# pcb-pick-plaz-control_v1d.net
KiCad netlist of a schematic drawn in EAGLE
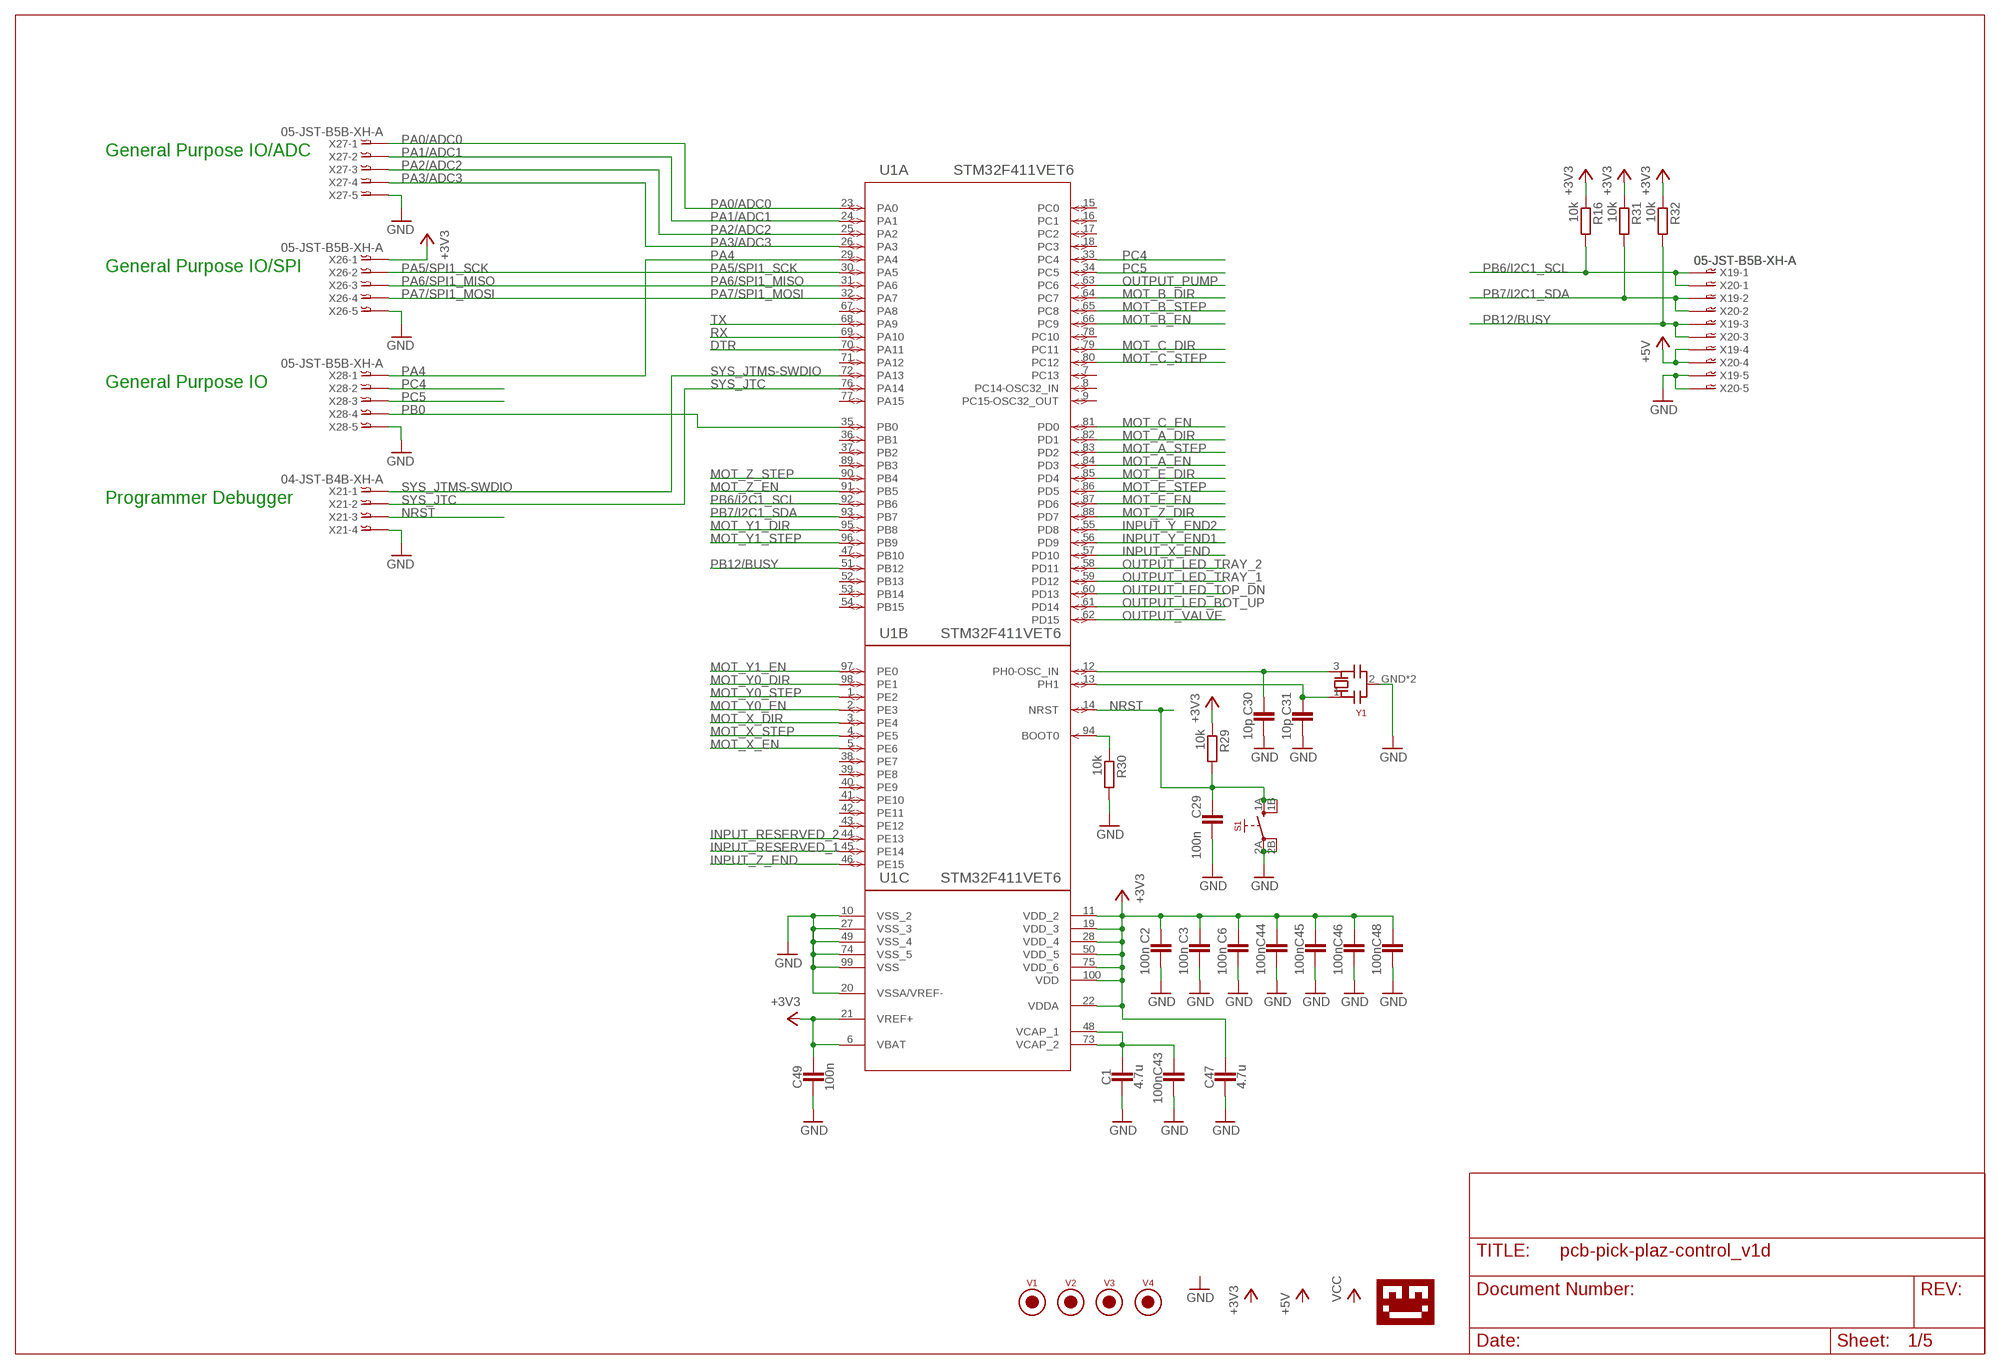
[diagram p0: schematic, sheet 1]
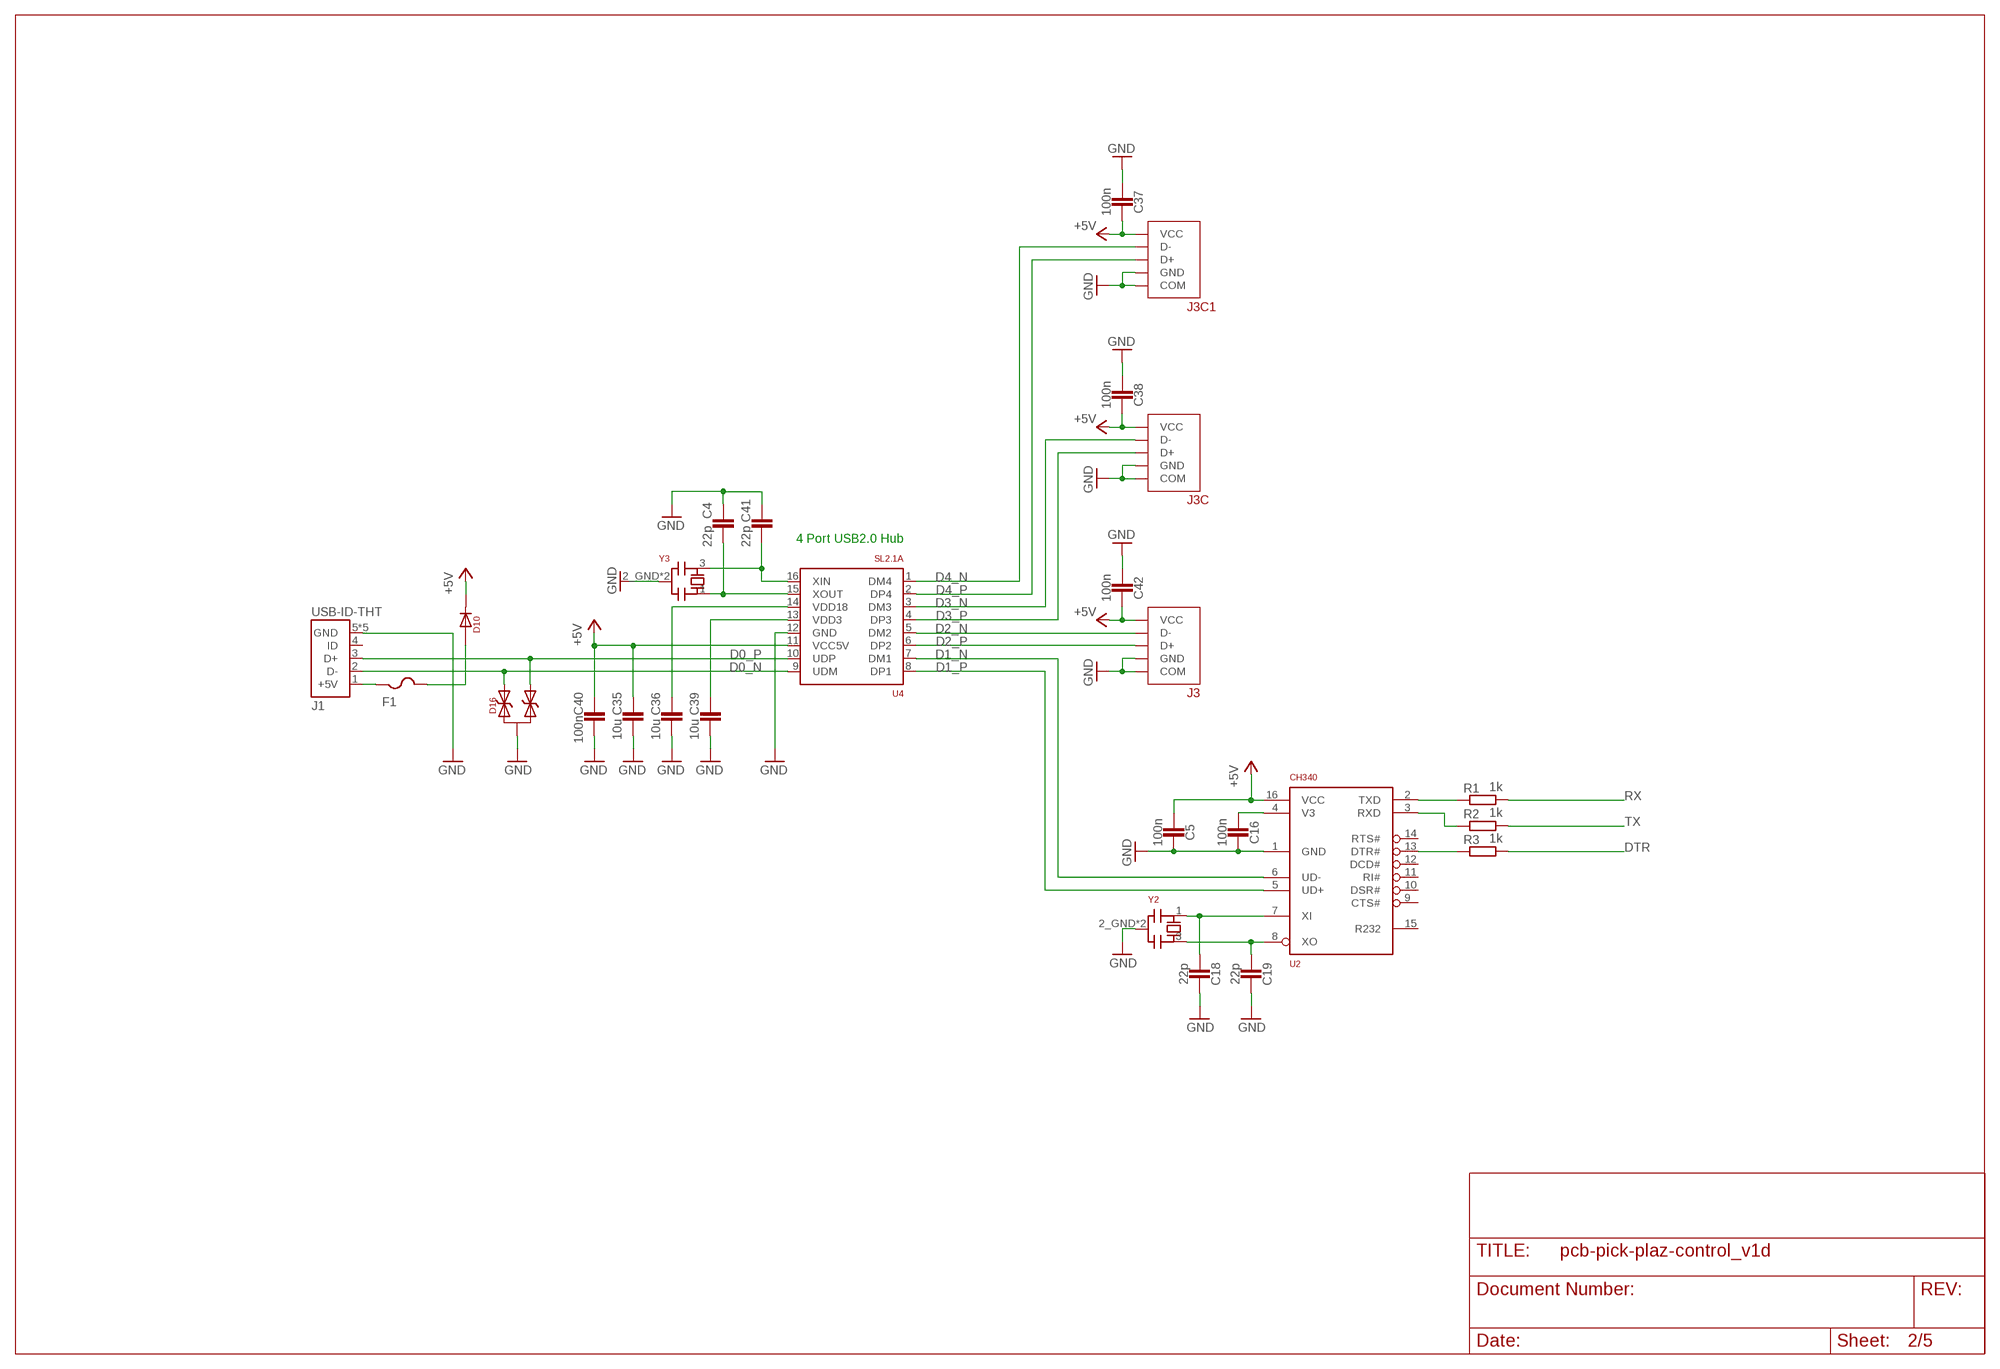
[diagram p1: schematic, sheet 2]
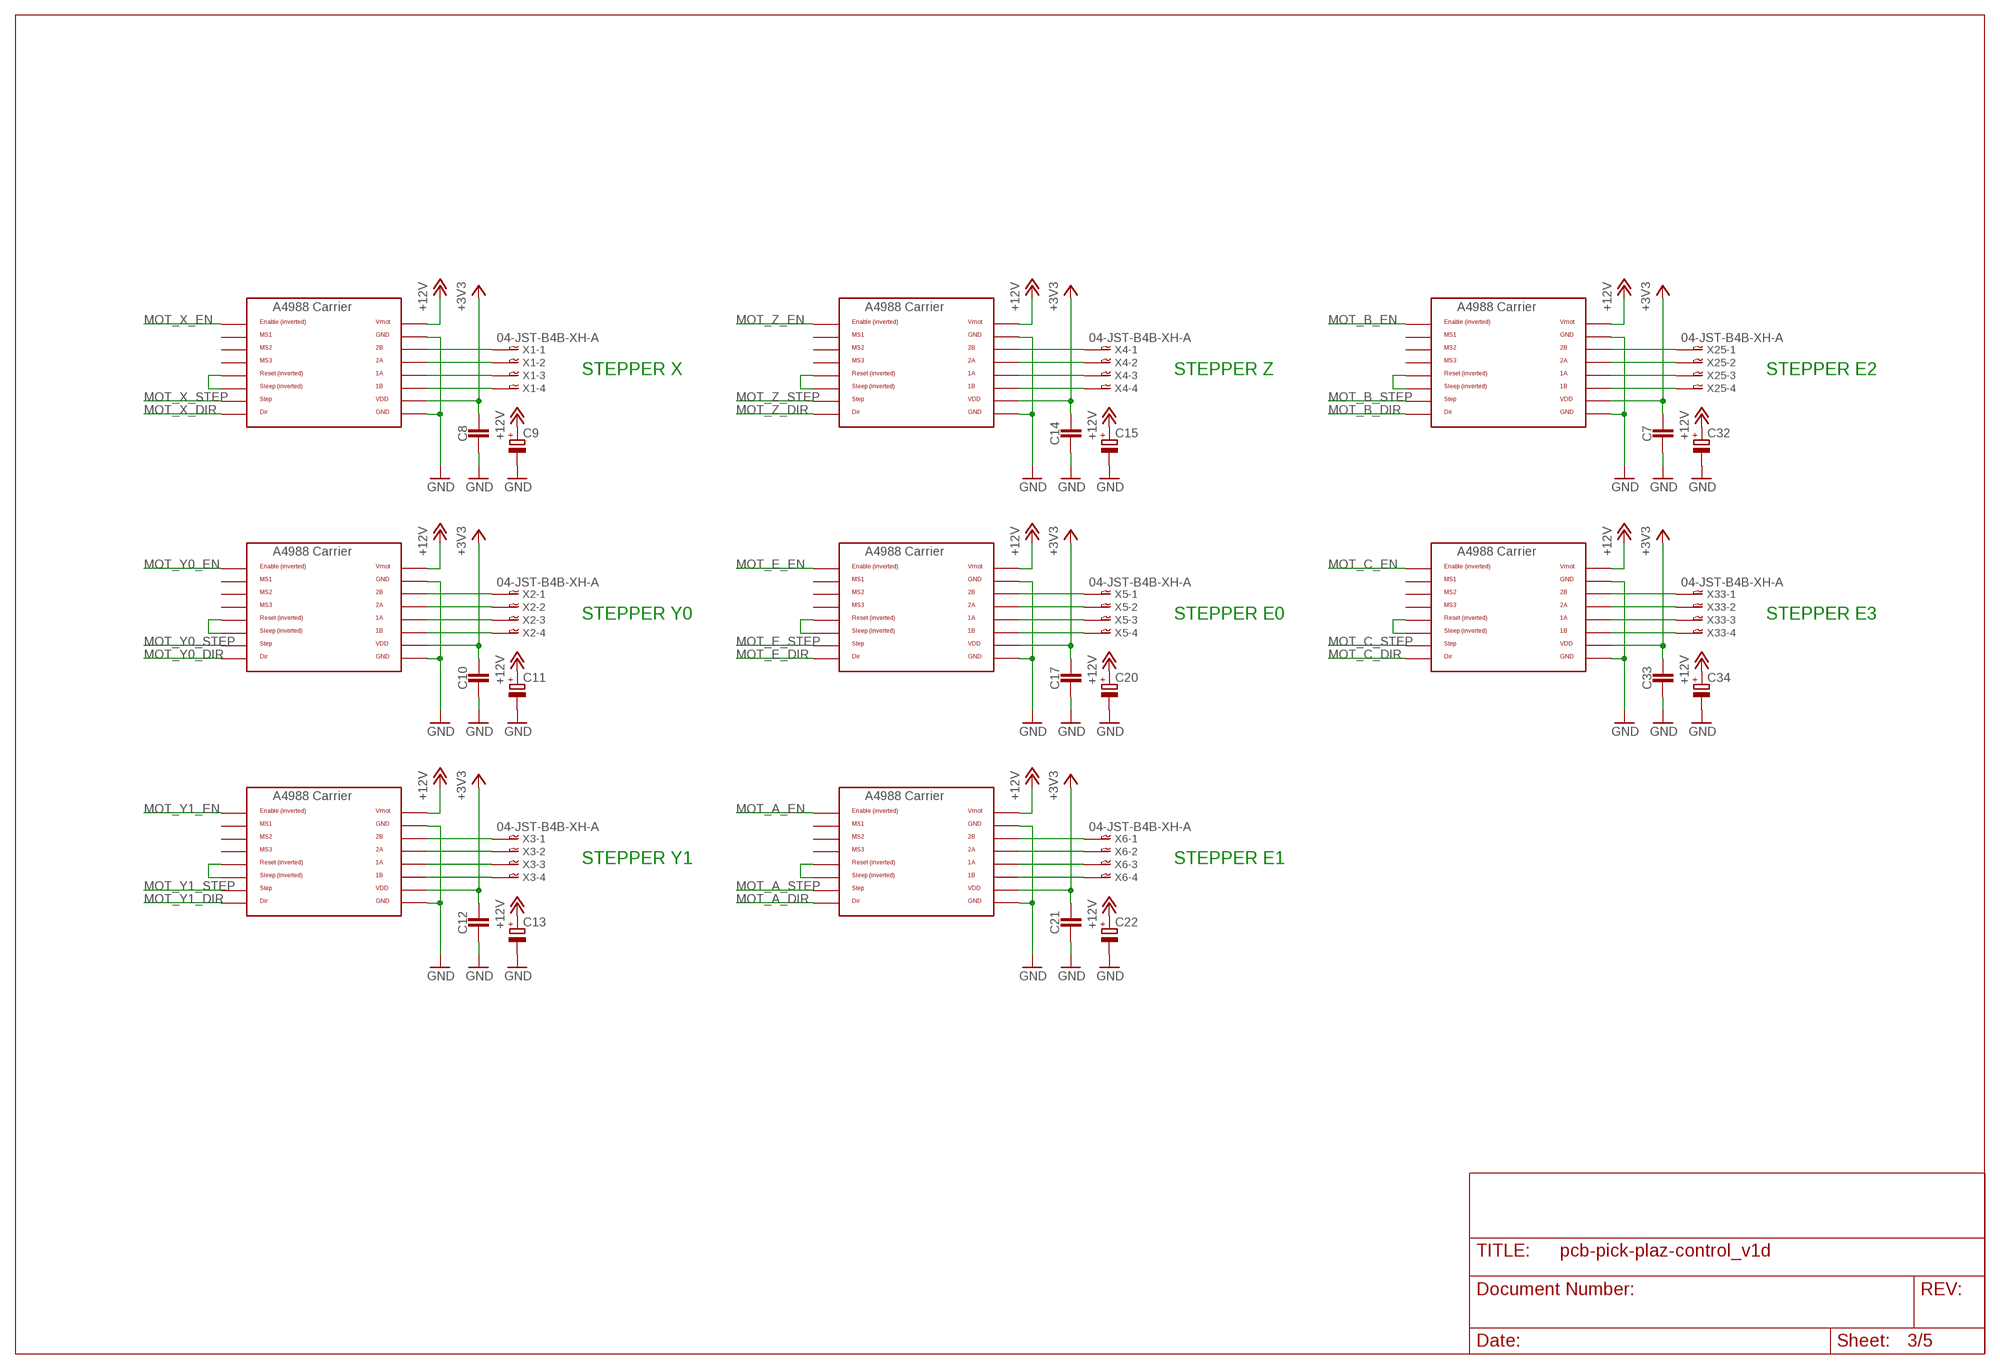
[diagram p2: schematic, sheet 3]
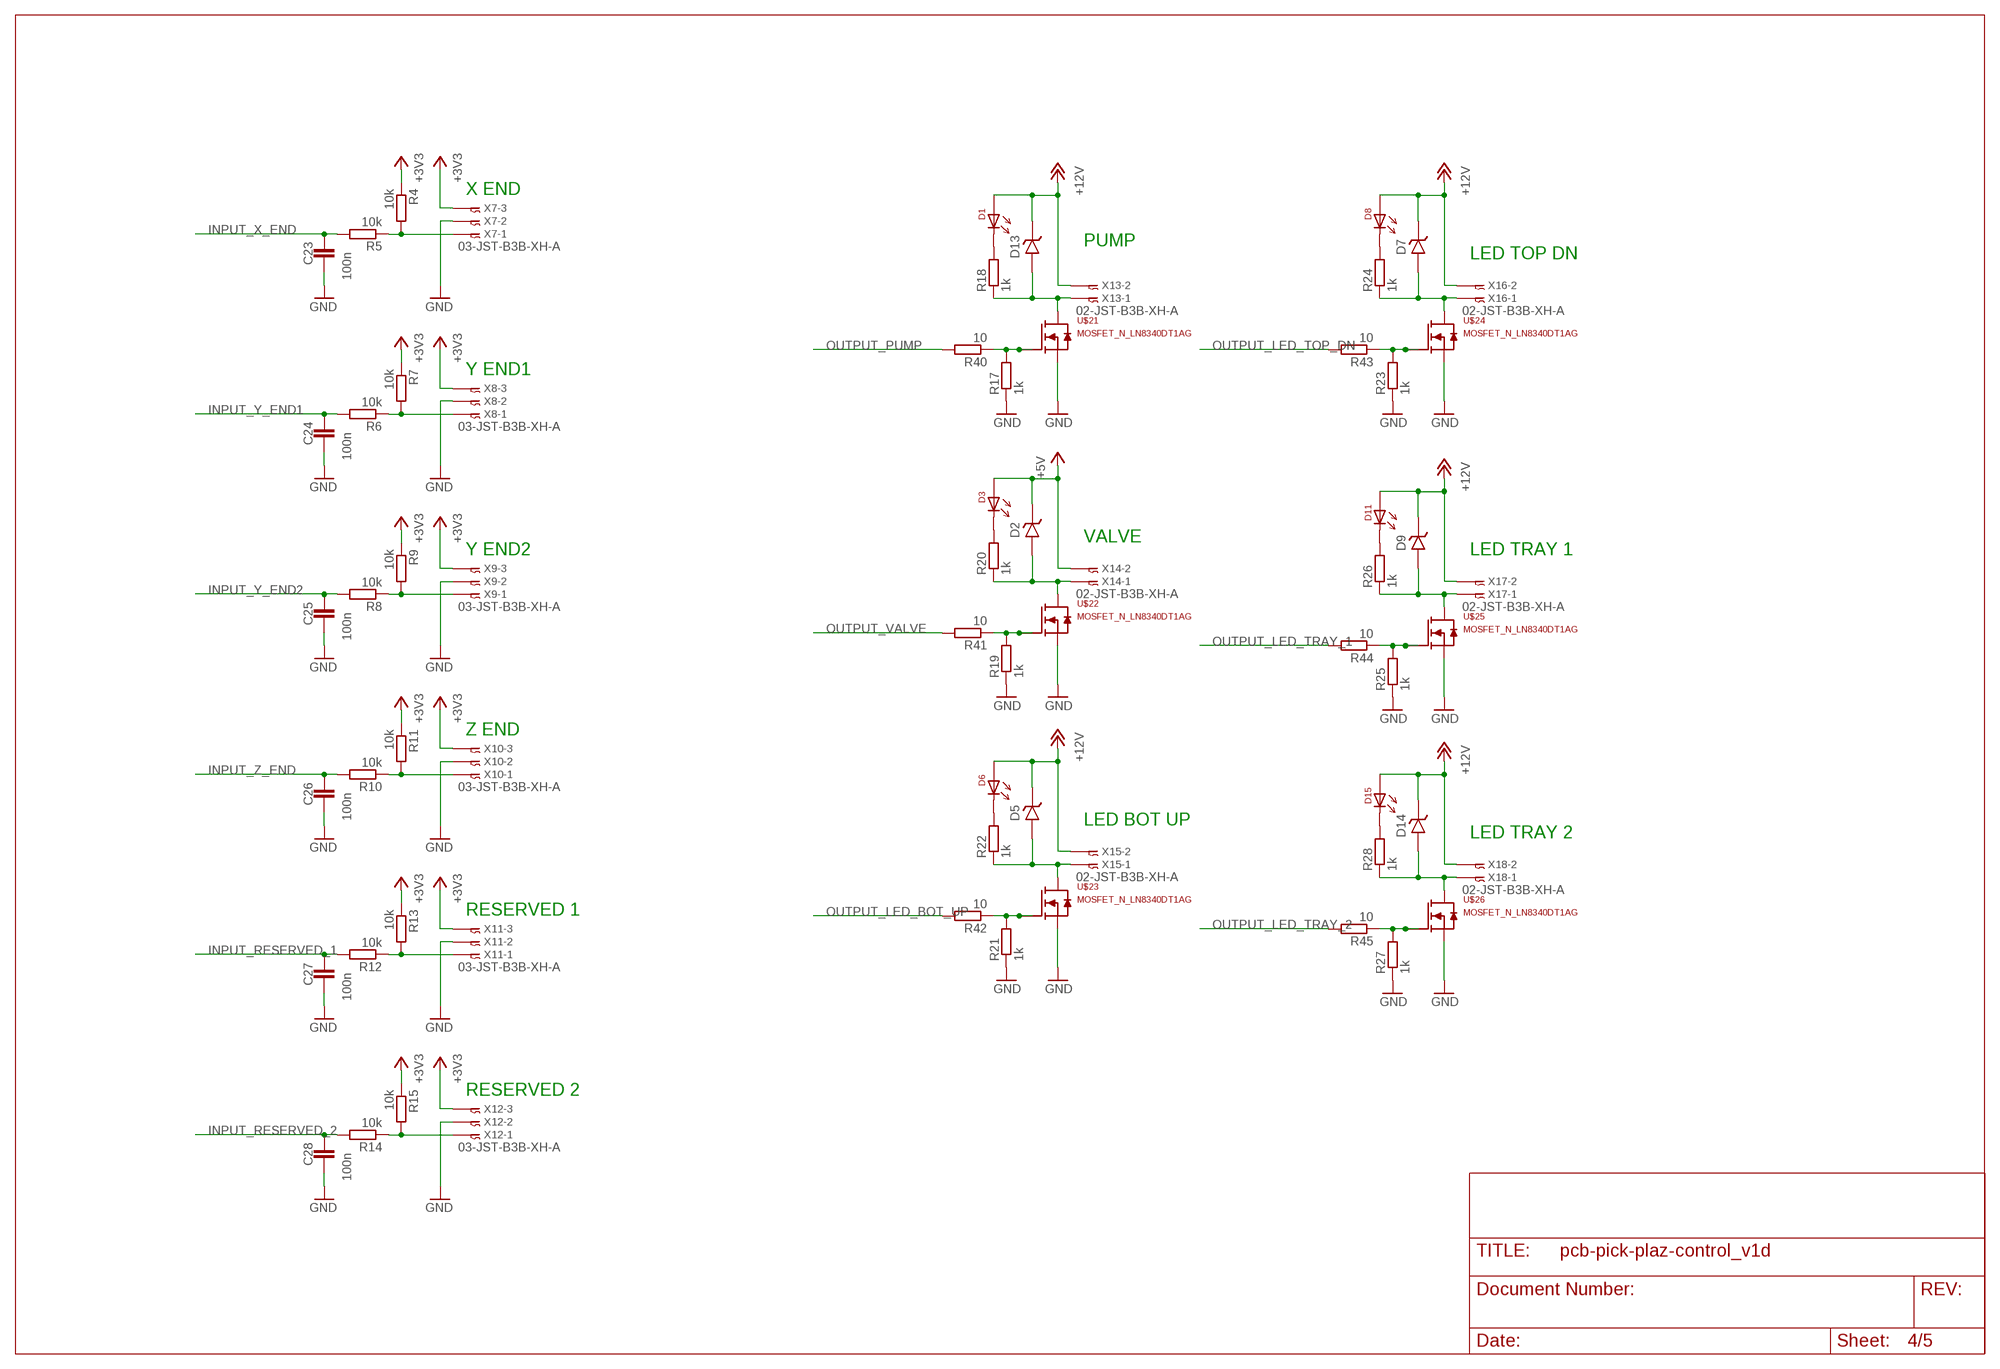
[diagram p3: schematic, sheet 4]
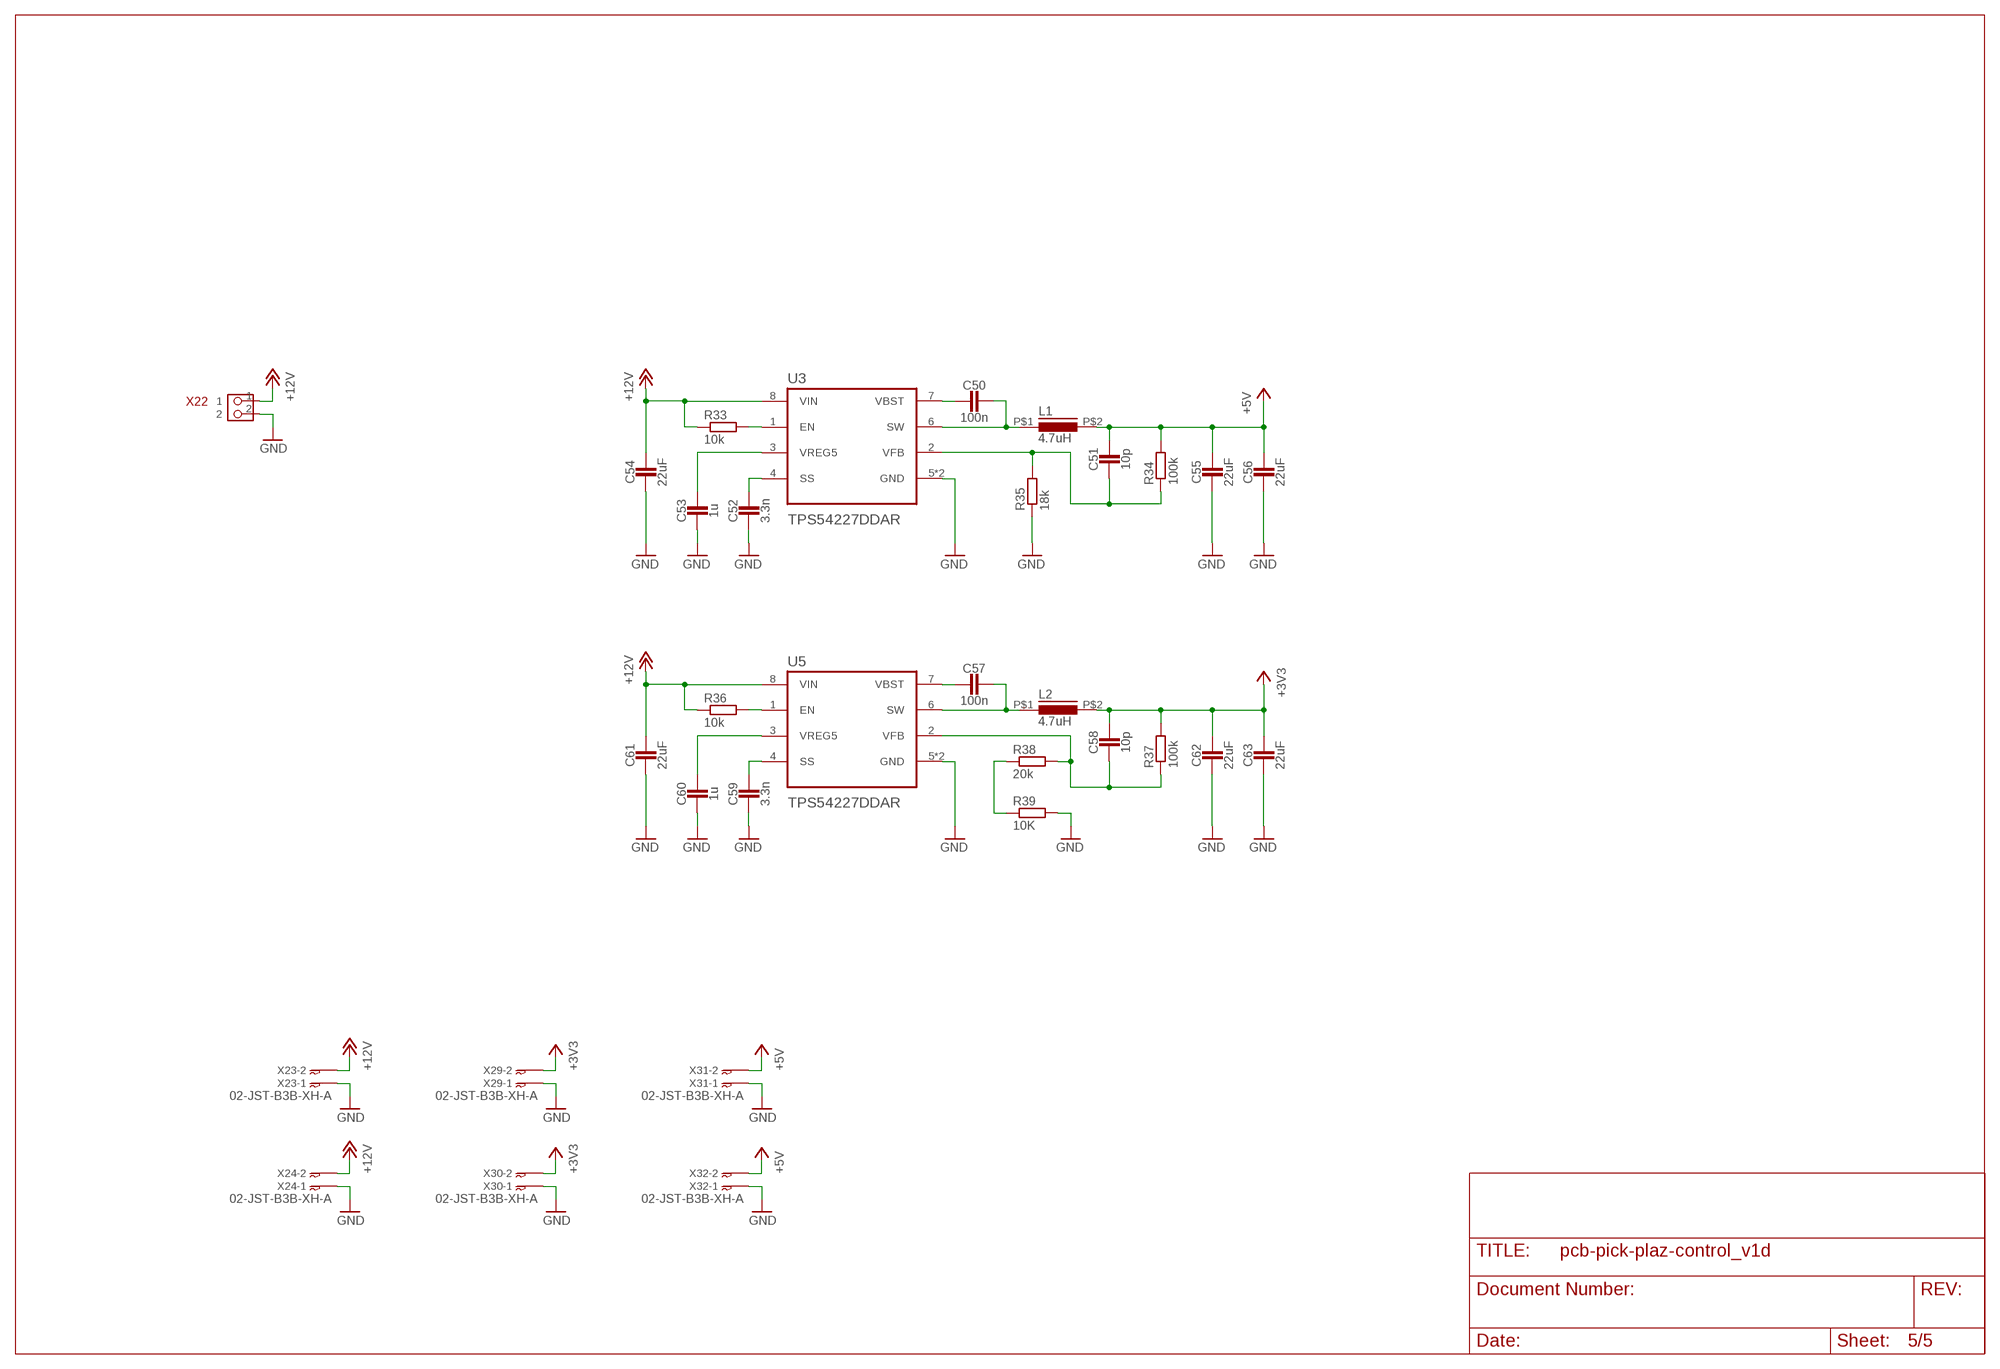
[diagram p4: schematic, sheet 5]

(export (version "E")
  (design (tool "Eeschema 10.0.6"))
  (components
    (comp (ref "C1")
      (value "4.7u")
      (footprint "eagle-import:0805_CAP")
      (libsource (lib "eagle-import") (part "CAPACITOR0805_CAP"))
    )
    (comp (ref "C2")
      (value "100n")
      (footprint "eagle-import:0603_CAP")
      (libsource (lib "eagle-import") (part "CAPACITOR0603_CAP"))
    )
    (comp (ref "C3")
      (value "100n")
      (footprint "eagle-import:0603_CAP")
      (libsource (lib "eagle-import") (part "CAPACITOR0603_CAP"))
    )
    (comp (ref "C6")
      (value "100n")
      (footprint "eagle-import:0603_CAP")
      (libsource (lib "eagle-import") (part "CAPACITOR0603_CAP"))
    )
    (comp (ref "C29")
      (value "100n")
      (footprint "eagle-import:0603_CAP")
      (libsource (lib "eagle-import") (part "CAPACITOR0603_CAP"))
    )
    (comp (ref "C30")
      (value "10p")
      (footprint "eagle-import:0603_CAP")
      (libsource (lib "eagle-import") (part "CAPACITOR0603_CAP"))
    )
    (comp (ref "C31")
      (value "10p")
      (footprint "eagle-import:0603_CAP")
      (libsource (lib "eagle-import") (part "CAPACITOR0603_CAP"))
    )
    (comp (ref "C43")
      (value "100n")
      (footprint "eagle-import:0603_CAP")
      (libsource (lib "eagle-import") (part "CAPACITOR0603_CAP"))
    )
    (comp (ref "C44")
      (value "100n")
      (footprint "eagle-import:0603_CAP")
      (libsource (lib "eagle-import") (part "CAPACITOR0603_CAP"))
    )
    (comp (ref "C45")
      (value "100n")
      (footprint "eagle-import:0603_CAP")
      (libsource (lib "eagle-import") (part "CAPACITOR0603_CAP"))
    )
    (comp (ref "C46")
      (value "100n")
      (footprint "eagle-import:0603_CAP")
      (libsource (lib "eagle-import") (part "CAPACITOR0603_CAP"))
    )
    (comp (ref "C47")
      (value "4.7u")
      (footprint "eagle-import:0805_CAP")
      (libsource (lib "eagle-import") (part "CAPACITOR0805_CAP"))
    )
    (comp (ref "C48")
      (value "100n")
      (footprint "eagle-import:0603_CAP")
      (libsource (lib "eagle-import") (part "CAPACITOR0603_CAP"))
    )
    (comp (ref "C49")
      (value "100n")
      (footprint "eagle-import:0603_CAP")
      (libsource (lib "eagle-import") (part "CAPACITOR0603_CAP"))
    )
    (comp (ref "R16")
      (value "10k")
      (footprint "eagle-import:0603-RES")
      (libsource (lib "eagle-import") (part "RESISTOR0603_RES"))
    )
    (comp (ref "R29")
      (value "10k")
      (footprint "eagle-import:0603-RES")
      (libsource (lib "eagle-import") (part "RESISTOR0603_RES"))
    )
    (comp (ref "R30")
      (value "10k")
      (footprint "eagle-import:0603-RES")
      (libsource (lib "eagle-import") (part "RESISTOR0603_RES"))
    )
    (comp (ref "R31")
      (value "10k")
      (footprint "eagle-import:0603-RES")
      (libsource (lib "eagle-import") (part "RESISTOR0603_RES"))
    )
    (comp (ref "R32")
      (value "10k")
      (footprint "eagle-import:0603-RES")
      (libsource (lib "eagle-import") (part "RESISTOR0603_RES"))
    )
    (comp (ref "S1")
      (value "SWITCH_2PD")
      (footprint "eagle-import:SWITCH_WH")
      (libsource (lib "eagle-import") (part "SWITCH_2PD"))
    )
    (comp (ref "U$1")
      (value "LOGO-TOBENG-1MM-FINISH")
      (footprint "eagle-import:TOBENG-1MM-FINISH")
      (libsource (lib "eagle-import") (part "LOGO-TOBENG-1MM-FINISH"))
    )
    (comp (ref "U1")
      (value "STM32F411VET6")
      (footprint "eagle-import:LQFP100-14X14MM")
      (fields (field (name "COPYRIGHT") "Copyright (C) 2018 Accelerated Designs. All rights reserved"))
      (libsource (lib "eagle-import") (part "STM32F411VET6"))
    )
    (comp (ref "V1")
      (value "FIDUCIAL2MM")
      (footprint "eagle-import:FIDUCIAL_2MM")
      (libsource (lib "eagle-import") (part "FIDUCIAL2MM"))
    )
    (comp (ref "V2")
      (value "FIDUCIAL2MM")
      (footprint "eagle-import:FIDUCIAL_2MM")
      (libsource (lib "eagle-import") (part "FIDUCIAL2MM"))
    )
    (comp (ref "V3")
      (value "FIDUCIAL2MM")
      (footprint "eagle-import:FIDUCIAL_2MM")
      (libsource (lib "eagle-import") (part "FIDUCIAL2MM"))
    )
    (comp (ref "V4")
      (value "FIDUCIAL2MM")
      (footprint "eagle-import:FIDUCIAL_2MM")
      (libsource (lib "eagle-import") (part "FIDUCIAL2MM"))
    )
    (comp (ref "X19")
      (value "05-JST-B5B-XH-A")
      (footprint "eagle-import:B5B-XH")
      (libsource (lib "eagle-import") (part "05-JST-B5B-XH-A"))
    )
    (comp (ref "X20")
      (value "05-JST-B5B-XH-A")
      (footprint "eagle-import:B5B-XH")
      (libsource (lib "eagle-import") (part "05-JST-B5B-XH-A"))
    )
    (comp (ref "X21")
      (value "04-JST-B4B-XH-A")
      (footprint "eagle-import:B4B-XH")
      (libsource (lib "eagle-import") (part "04-JST-B4B-XH-A"))
    )
    (comp (ref "X26")
      (value "05-JST-B5B-XH-A")
      (footprint "eagle-import:B5B-XH")
      (libsource (lib "eagle-import") (part "05-JST-B5B-XH-A"))
    )
    (comp (ref "X27")
      (value "05-JST-B5B-XH-A")
      (footprint "eagle-import:B5B-XH")
      (libsource (lib "eagle-import") (part "05-JST-B5B-XH-A"))
    )
    (comp (ref "X28")
      (value "05-JST-B5B-XH-A")
      (footprint "eagle-import:B5B-XH")
      (libsource (lib "eagle-import") (part "05-JST-B5B-XH-A"))
    )
    (comp (ref "Y1")
      (value "3213-QUARZ3225")
      (footprint "eagle-import:3225-QUARZ")
      (libsource (lib "eagle-import") (part "3213-QUARZ3225"))
    )
    (comp (ref "C4")
      (value "22p")
      (footprint "eagle-import:0603_CAP")
      (libsource (lib "eagle-import") (part "CAPACITOR0603_CAP"))
    )
    (comp (ref "C5")
      (value "100n")
      (footprint "eagle-import:0603_CAP")
      (libsource (lib "eagle-import") (part "CAPACITOR0603_CAP"))
    )
    (comp (ref "C16")
      (value "100n")
      (footprint "eagle-import:0603_CAP")
      (libsource (lib "eagle-import") (part "CAPACITOR0603_CAP"))
    )
    (comp (ref "C18")
      (value "22p")
      (footprint "eagle-import:0603_CAP")
      (libsource (lib "eagle-import") (part "CAPACITOR0603_CAP"))
    )
    (comp (ref "C19")
      (value "22p")
      (footprint "eagle-import:0603_CAP")
      (libsource (lib "eagle-import") (part "CAPACITOR0603_CAP"))
    )
    (comp (ref "C35")
      (value "10u")
      (footprint "eagle-import:0805_CAP")
      (libsource (lib "eagle-import") (part "CAPACITOR0805_CAP"))
    )
    (comp (ref "C36")
      (value "10u")
      (footprint "eagle-import:0805_CAP")
      (libsource (lib "eagle-import") (part "CAPACITOR0805_CAP"))
    )
    (comp (ref "C37")
      (value "100n")
      (footprint "eagle-import:0603_CAP")
      (libsource (lib "eagle-import") (part "CAPACITOR0603_CAP"))
    )
    (comp (ref "C38")
      (value "100n")
      (footprint "eagle-import:0603_CAP")
      (libsource (lib "eagle-import") (part "CAPACITOR0603_CAP"))
    )
    (comp (ref "C39")
      (value "10u")
      (footprint "eagle-import:0805_CAP")
      (libsource (lib "eagle-import") (part "CAPACITOR0805_CAP"))
    )
    (comp (ref "C40")
      (value "100n")
      (footprint "eagle-import:0603_CAP")
      (libsource (lib "eagle-import") (part "CAPACITOR0603_CAP"))
    )
    (comp (ref "C41")
      (value "22p")
      (footprint "eagle-import:0603_CAP")
      (libsource (lib "eagle-import") (part "CAPACITOR0603_CAP"))
    )
    (comp (ref "C42")
      (value "100n")
      (footprint "eagle-import:0603_CAP")
      (libsource (lib "eagle-import") (part "CAPACITOR0603_CAP"))
    )
    (comp (ref "D10")
      (value "DIODE-1206")
      (footprint "eagle-import:1206-DOT")
      (libsource (lib "eagle-import") (part "DIODE-1206"))
    )
    (comp (ref "D16")
      (value "DIODE-TVS")
      (footprint "eagle-import:SOT-23")
      (libsource (lib "eagle-import") (part "DIODE-TVS"))
    )
    (comp (ref "F1")
      (value "PTCFUSE-1206")
      (footprint "eagle-import:R1206")
      (libsource (lib "eagle-import") (part "PTCFUSE-1206"))
    )
    (comp (ref "J1")
      (value "USB-ID-THT")
      (footprint "eagle-import:USB-MICRO-THT")
      (libsource (lib "eagle-import") (part "USB-ID-THT"))
    )
    (comp (ref "J3")
      (value "USB-LCSC_C42431")
      (footprint "eagle-import:USB-A-LCSC_C42431")
      (libsource (lib "eagle-import") (part "USB-LCSC_C42431"))
    )
    (comp (ref "J3C")
      (value "USB-LCSC_C42431")
      (footprint "eagle-import:USB-A-LCSC_C42431")
      (libsource (lib "eagle-import") (part "USB-LCSC_C42431"))
    )
    (comp (ref "J3C1")
      (value "USB-LCSC_C42431")
      (footprint "eagle-import:USB-A-LCSC_C42431")
      (libsource (lib "eagle-import") (part "USB-LCSC_C42431"))
    )
    (comp (ref "R1")
      (value "1k")
      (footprint "eagle-import:0603-RES")
      (libsource (lib "eagle-import") (part "RESISTOR0603_RES"))
    )
    (comp (ref "R2")
      (value "1k")
      (footprint "eagle-import:0603-RES")
      (libsource (lib "eagle-import") (part "RESISTOR0603_RES"))
    )
    (comp (ref "R3")
      (value "1k")
      (footprint "eagle-import:0603-RES")
      (libsource (lib "eagle-import") (part "RESISTOR0603_RES"))
    )
    (comp (ref "U2")
      (value "CH340")
      (footprint "eagle-import:SOIC-16")
      (libsource (lib "eagle-import") (part "CH340"))
    )
    (comp (ref "U4")
      (value "SL2.1A")
      (footprint "eagle-import:SOIC-16")
      (libsource (lib "eagle-import") (part "SL2.1A"))
    )
    (comp (ref "Y2")
      (value "3213-QUARZ3225")
      (footprint "eagle-import:3225-QUARZ")
      (libsource (lib "eagle-import") (part "3213-QUARZ3225"))
    )
    (comp (ref "Y3")
      (value "3213-QUARZ3225")
      (footprint "eagle-import:3225-QUARZ")
      (libsource (lib "eagle-import") (part "3213-QUARZ3225"))
    )
    (comp (ref "C7")
      (value "CAPACITOR0603_CAP")
      (footprint "eagle-import:0603_CAP")
      (libsource (lib "eagle-import") (part "CAPACITOR0603_CAP"))
    )
    (comp (ref "C8")
      (value "CAPACITOR0603_CAP")
      (footprint "eagle-import:0603_CAP")
      (libsource (lib "eagle-import") (part "CAPACITOR0603_CAP"))
    )
    (comp (ref "C9")
      (value "CPOL-EU175TMP-0808")
      (footprint "eagle-import:175TMP-0808")
      (libsource (lib "eagle-import") (part "CPOL-EU175TMP-0808"))
    )
    (comp (ref "C10")
      (value "CAPACITOR0603_CAP")
      (footprint "eagle-import:0603_CAP")
      (libsource (lib "eagle-import") (part "CAPACITOR0603_CAP"))
    )
    (comp (ref "C11")
      (value "CPOL-EU175TMP-0808")
      (footprint "eagle-import:175TMP-0808")
      (libsource (lib "eagle-import") (part "CPOL-EU175TMP-0808"))
    )
    (comp (ref "C12")
      (value "CAPACITOR0603_CAP")
      (footprint "eagle-import:0603_CAP")
      (libsource (lib "eagle-import") (part "CAPACITOR0603_CAP"))
    )
    (comp (ref "C13")
      (value "CPOL-EU175TMP-0808")
      (footprint "eagle-import:175TMP-0808")
      (libsource (lib "eagle-import") (part "CPOL-EU175TMP-0808"))
    )
    (comp (ref "C14")
      (value "CAPACITOR0603_CAP")
      (footprint "eagle-import:0603_CAP")
      (libsource (lib "eagle-import") (part "CAPACITOR0603_CAP"))
    )
    (comp (ref "C15")
      (value "CPOL-EU175TMP-0808")
      (footprint "eagle-import:175TMP-0808")
      (libsource (lib "eagle-import") (part "CPOL-EU175TMP-0808"))
    )
    (comp (ref "C17")
      (value "CAPACITOR0603_CAP")
      (footprint "eagle-import:0603_CAP")
      (libsource (lib "eagle-import") (part "CAPACITOR0603_CAP"))
    )
    (comp (ref "C20")
      (value "CPOL-EU175TMP-0808")
      (footprint "eagle-import:175TMP-0808")
      (libsource (lib "eagle-import") (part "CPOL-EU175TMP-0808"))
    )
    (comp (ref "C21")
      (value "CAPACITOR0603_CAP")
      (footprint "eagle-import:0603_CAP")
      (libsource (lib "eagle-import") (part "CAPACITOR0603_CAP"))
    )
    (comp (ref "C22")
      (value "CPOL-EU175TMP-0808")
      (footprint "eagle-import:175TMP-0808")
      (libsource (lib "eagle-import") (part "CPOL-EU175TMP-0808"))
    )
    (comp (ref "C32")
      (value "CPOL-EU175TMP-0808")
      (footprint "eagle-import:175TMP-0808")
      (libsource (lib "eagle-import") (part "CPOL-EU175TMP-0808"))
    )
    (comp (ref "C33")
      (value "CAPACITOR0603_CAP")
      (footprint "eagle-import:0603_CAP")
      (libsource (lib "eagle-import") (part "CAPACITOR0603_CAP"))
    )
    (comp (ref "C34")
      (value "CPOL-EU175TMP-0808")
      (footprint "eagle-import:175TMP-0808")
      (libsource (lib "eagle-import") (part "CPOL-EU175TMP-0808"))
    )
    (comp (ref "U$2")
      (value "A4988BREAKOUT")
      (footprint "eagle-import:A4988BREAKOUT")
      (libsource (lib "eagle-import") (part "A4988BREAKOUT"))
    )
    (comp (ref "U$3")
      (value "A4988BREAKOUT")
      (footprint "eagle-import:A4988BREAKOUT")
      (libsource (lib "eagle-import") (part "A4988BREAKOUT"))
    )
    (comp (ref "U$4")
      (value "A4988BREAKOUT")
      (footprint "eagle-import:A4988BREAKOUT")
      (libsource (lib "eagle-import") (part "A4988BREAKOUT"))
    )
    (comp (ref "U$5")
      (value "A4988BREAKOUT")
      (footprint "eagle-import:A4988BREAKOUT")
      (libsource (lib "eagle-import") (part "A4988BREAKOUT"))
    )
    (comp (ref "U$6")
      (value "A4988BREAKOUT")
      (footprint "eagle-import:A4988BREAKOUT")
      (libsource (lib "eagle-import") (part "A4988BREAKOUT"))
    )
    (comp (ref "U$7")
      (value "A4988BREAKOUT")
      (footprint "eagle-import:A4988BREAKOUT")
      (libsource (lib "eagle-import") (part "A4988BREAKOUT"))
    )
    (comp (ref "U$8")
      (value "A4988BREAKOUT")
      (footprint "eagle-import:A4988BREAKOUT")
      (libsource (lib "eagle-import") (part "A4988BREAKOUT"))
    )
    (comp (ref "U$9")
      (value "A4988BREAKOUT")
      (footprint "eagle-import:A4988BREAKOUT")
      (libsource (lib "eagle-import") (part "A4988BREAKOUT"))
    )
    (comp (ref "X1")
      (value "04-JST-B4B-XH-A")
      (footprint "eagle-import:B4B-XH")
      (libsource (lib "eagle-import") (part "04-JST-B4B-XH-A"))
    )
    (comp (ref "X2")
      (value "04-JST-B4B-XH-A")
      (footprint "eagle-import:B4B-XH")
      (libsource (lib "eagle-import") (part "04-JST-B4B-XH-A"))
    )
    (comp (ref "X3")
      (value "04-JST-B4B-XH-A")
      (footprint "eagle-import:B4B-XH")
      (libsource (lib "eagle-import") (part "04-JST-B4B-XH-A"))
    )
    (comp (ref "X4")
      (value "04-JST-B4B-XH-A")
      (footprint "eagle-import:B4B-XH")
      (libsource (lib "eagle-import") (part "04-JST-B4B-XH-A"))
    )
    (comp (ref "X5")
      (value "04-JST-B4B-XH-A")
      (footprint "eagle-import:B4B-XH")
      (libsource (lib "eagle-import") (part "04-JST-B4B-XH-A"))
    )
    (comp (ref "X6")
      (value "04-JST-B4B-XH-A")
      (footprint "eagle-import:B4B-XH")
      (libsource (lib "eagle-import") (part "04-JST-B4B-XH-A"))
    )
    (comp (ref "X25")
      (value "04-JST-B4B-XH-A")
      (footprint "eagle-import:B4B-XH")
      (libsource (lib "eagle-import") (part "04-JST-B4B-XH-A"))
    )
    (comp (ref "X33")
      (value "04-JST-B4B-XH-A")
      (footprint "eagle-import:B4B-XH")
      (libsource (lib "eagle-import") (part "04-JST-B4B-XH-A"))
    )
    (comp (ref "C23")
      (value "100n")
      (footprint "eagle-import:0603_CAP")
      (libsource (lib "eagle-import") (part "CAPACITOR0603_CAP"))
    )
    (comp (ref "C24")
      (value "100n")
      (footprint "eagle-import:0603_CAP")
      (libsource (lib "eagle-import") (part "CAPACITOR0603_CAP"))
    )
    (comp (ref "C25")
      (value "100n")
      (footprint "eagle-import:0603_CAP")
      (libsource (lib "eagle-import") (part "CAPACITOR0603_CAP"))
    )
    (comp (ref "C26")
      (value "100n")
      (footprint "eagle-import:0603_CAP")
      (libsource (lib "eagle-import") (part "CAPACITOR0603_CAP"))
    )
    (comp (ref "C27")
      (value "100n")
      (footprint "eagle-import:0603_CAP")
      (libsource (lib "eagle-import") (part "CAPACITOR0603_CAP"))
    )
    (comp (ref "C28")
      (value "100n")
      (footprint "eagle-import:0603_CAP")
      (libsource (lib "eagle-import") (part "CAPACITOR0603_CAP"))
    )
    (comp (ref "D1")
      (value "LED-0805")
      (footprint "eagle-import:0805-DOT")
      (libsource (lib "eagle-import") (part "LED-0805"))
    )
    (comp (ref "D2")
      (value "DIODE_ZENERSOD123")
      (footprint "eagle-import:SOD123")
      (libsource (lib "eagle-import") (part "DIODE_ZENERSOD123"))
    )
    (comp (ref "D3")
      (value "LED-0805")
      (footprint "eagle-import:0805-DOT")
      (libsource (lib "eagle-import") (part "LED-0805"))
    )
    (comp (ref "D5")
      (value "DIODE_ZENERSOD123")
      (footprint "eagle-import:SOD123")
      (libsource (lib "eagle-import") (part "DIODE_ZENERSOD123"))
    )
    (comp (ref "D6")
      (value "LED-0805")
      (footprint "eagle-import:0805-DOT")
      (libsource (lib "eagle-import") (part "LED-0805"))
    )
    (comp (ref "D7")
      (value "DIODE_ZENERSOD123")
      (footprint "eagle-import:SOD123")
      (libsource (lib "eagle-import") (part "DIODE_ZENERSOD123"))
    )
    (comp (ref "D8")
      (value "LED-0805")
      (footprint "eagle-import:0805-DOT")
      (libsource (lib "eagle-import") (part "LED-0805"))
    )
    (comp (ref "D9")
      (value "DIODE_ZENERSOD123")
      (footprint "eagle-import:SOD123")
      (libsource (lib "eagle-import") (part "DIODE_ZENERSOD123"))
    )
    (comp (ref "D11")
      (value "LED-0805")
      (footprint "eagle-import:0805-DOT")
      (libsource (lib "eagle-import") (part "LED-0805"))
    )
    (comp (ref "D13")
      (value "DIODE_ZENERSOD123")
      (footprint "eagle-import:SOD123")
      (libsource (lib "eagle-import") (part "DIODE_ZENERSOD123"))
    )
    (comp (ref "D14")
      (value "DIODE_ZENERSOD123")
      (footprint "eagle-import:SOD123")
      (libsource (lib "eagle-import") (part "DIODE_ZENERSOD123"))
    )
    (comp (ref "D15")
      (value "LED-0805")
      (footprint "eagle-import:0805-DOT")
      (libsource (lib "eagle-import") (part "LED-0805"))
    )
    (comp (ref "R4")
      (value "10k")
      (footprint "eagle-import:0603-RES")
      (libsource (lib "eagle-import") (part "RESISTOR0603_RES"))
    )
    (comp (ref "R5")
      (value "10k")
      (footprint "eagle-import:0603-RES")
      (libsource (lib "eagle-import") (part "RESISTOR0603_RES"))
    )
    (comp (ref "R6")
      (value "10k")
      (footprint "eagle-import:0603-RES")
      (libsource (lib "eagle-import") (part "RESISTOR0603_RES"))
    )
    (comp (ref "R7")
      (value "10k")
      (footprint "eagle-import:0603-RES")
      (libsource (lib "eagle-import") (part "RESISTOR0603_RES"))
    )
    (comp (ref "R8")
      (value "10k")
      (footprint "eagle-import:0603-RES")
      (libsource (lib "eagle-import") (part "RESISTOR0603_RES"))
    )
    (comp (ref "R9")
      (value "10k")
      (footprint "eagle-import:0603-RES")
      (libsource (lib "eagle-import") (part "RESISTOR0603_RES"))
    )
    (comp (ref "R10")
      (value "10k")
      (footprint "eagle-import:0603-RES")
      (libsource (lib "eagle-import") (part "RESISTOR0603_RES"))
    )
    (comp (ref "R11")
      (value "10k")
      (footprint "eagle-import:0603-RES")
      (libsource (lib "eagle-import") (part "RESISTOR0603_RES"))
    )
    (comp (ref "R12")
      (value "10k")
      (footprint "eagle-import:0603-RES")
      (libsource (lib "eagle-import") (part "RESISTOR0603_RES"))
    )
    (comp (ref "R13")
      (value "10k")
      (footprint "eagle-import:0603-RES")
      (libsource (lib "eagle-import") (part "RESISTOR0603_RES"))
    )
    (comp (ref "R14")
      (value "10k")
      (footprint "eagle-import:0603-RES")
      (libsource (lib "eagle-import") (part "RESISTOR0603_RES"))
    )
    (comp (ref "R15")
      (value "10k")
      (footprint "eagle-import:0603-RES")
      (libsource (lib "eagle-import") (part "RESISTOR0603_RES"))
    )
    (comp (ref "R17")
      (value "1k")
      (footprint "eagle-import:0603-RES")
      (libsource (lib "eagle-import") (part "RESISTOR0603_RES"))
    )
    (comp (ref "R18")
      (value "1k")
      (footprint "eagle-import:0603-RES")
      (libsource (lib "eagle-import") (part "RESISTOR0603_RES"))
    )
    (comp (ref "R19")
      (value "1k")
      (footprint "eagle-import:0603-RES")
      (libsource (lib "eagle-import") (part "RESISTOR0603_RES"))
    )
    (comp (ref "R20")
      (value "1k")
      (footprint "eagle-import:0603-RES")
      (libsource (lib "eagle-import") (part "RESISTOR0603_RES"))
    )
    (comp (ref "R21")
      (value "1k")
      (footprint "eagle-import:0603-RES")
      (libsource (lib "eagle-import") (part "RESISTOR0603_RES"))
    )
    (comp (ref "R22")
      (value "1k")
      (footprint "eagle-import:0603-RES")
      (libsource (lib "eagle-import") (part "RESISTOR0603_RES"))
    )
    (comp (ref "R23")
      (value "1k")
      (footprint "eagle-import:0603-RES")
      (libsource (lib "eagle-import") (part "RESISTOR0603_RES"))
    )
    (comp (ref "R24")
      (value "1k")
      (footprint "eagle-import:0603-RES")
      (libsource (lib "eagle-import") (part "RESISTOR0603_RES"))
    )
    (comp (ref "R25")
      (value "1k")
      (footprint "eagle-import:0603-RES")
      (libsource (lib "eagle-import") (part "RESISTOR0603_RES"))
    )
    (comp (ref "R26")
      (value "1k")
      (footprint "eagle-import:0603-RES")
      (libsource (lib "eagle-import") (part "RESISTOR0603_RES"))
    )
    (comp (ref "R27")
      (value "1k")
      (footprint "eagle-import:0603-RES")
      (libsource (lib "eagle-import") (part "RESISTOR0603_RES"))
    )
    (comp (ref "R28")
      (value "1k")
      (footprint "eagle-import:0603-RES")
      (libsource (lib "eagle-import") (part "RESISTOR0603_RES"))
    )
    (comp (ref "R40")
      (value "10")
      (footprint "eagle-import:0603-RES")
      (libsource (lib "eagle-import") (part "RESISTOR0603_RES"))
    )
    (comp (ref "R41")
      (value "10")
      (footprint "eagle-import:0603-RES")
      (libsource (lib "eagle-import") (part "RESISTOR0603_RES"))
    )
    (comp (ref "R42")
      (value "10")
      (footprint "eagle-import:0603-RES")
      (libsource (lib "eagle-import") (part "RESISTOR0603_RES"))
    )
    (comp (ref "R43")
      (value "10")
      (footprint "eagle-import:0603-RES")
      (libsource (lib "eagle-import") (part "RESISTOR0603_RES"))
    )
    (comp (ref "R44")
      (value "10")
      (footprint "eagle-import:0603-RES")
      (libsource (lib "eagle-import") (part "RESISTOR0603_RES"))
    )
    (comp (ref "R45")
      (value "10")
      (footprint "eagle-import:0603-RES")
      (libsource (lib "eagle-import") (part "RESISTOR0603_RES"))
    )
    (comp (ref "U$21")
      (value "MOSFET_N_LN8340DT1AG")
      (footprint "eagle-import:DFN3030-8B")
      (libsource (lib "eagle-import") (part "MOSFET_N_LN8340DT1AG"))
    )
    (comp (ref "U$22")
      (value "MOSFET_N_LN8340DT1AG")
      (footprint "eagle-import:DFN3030-8B")
      (libsource (lib "eagle-import") (part "MOSFET_N_LN8340DT1AG"))
    )
    (comp (ref "U$23")
      (value "MOSFET_N_LN8340DT1AG")
      (footprint "eagle-import:DFN3030-8B")
      (libsource (lib "eagle-import") (part "MOSFET_N_LN8340DT1AG"))
    )
    (comp (ref "U$24")
      (value "MOSFET_N_LN8340DT1AG")
      (footprint "eagle-import:DFN3030-8B")
      (libsource (lib "eagle-import") (part "MOSFET_N_LN8340DT1AG"))
    )
    (comp (ref "U$25")
      (value "MOSFET_N_LN8340DT1AG")
      (footprint "eagle-import:DFN3030-8B")
      (libsource (lib "eagle-import") (part "MOSFET_N_LN8340DT1AG"))
    )
    (comp (ref "U$26")
      (value "MOSFET_N_LN8340DT1AG")
      (footprint "eagle-import:DFN3030-8B")
      (libsource (lib "eagle-import") (part "MOSFET_N_LN8340DT1AG"))
    )
    (comp (ref "X7")
      (value "03-JST-B3B-XH-A")
      (footprint "eagle-import:B3B-XH")
      (libsource (lib "eagle-import") (part "03-JST-B3B-XH-A"))
    )
    (comp (ref "X8")
      (value "03-JST-B3B-XH-A")
      (footprint "eagle-import:B3B-XH")
      (libsource (lib "eagle-import") (part "03-JST-B3B-XH-A"))
    )
    (comp (ref "X9")
      (value "03-JST-B3B-XH-A")
      (footprint "eagle-import:B3B-XH")
      (libsource (lib "eagle-import") (part "03-JST-B3B-XH-A"))
    )
    (comp (ref "X10")
      (value "03-JST-B3B-XH-A")
      (footprint "eagle-import:B3B-XH")
      (libsource (lib "eagle-import") (part "03-JST-B3B-XH-A"))
    )
    (comp (ref "X11")
      (value "03-JST-B3B-XH-A")
      (footprint "eagle-import:B3B-XH")
      (libsource (lib "eagle-import") (part "03-JST-B3B-XH-A"))
    )
    (comp (ref "X12")
      (value "03-JST-B3B-XH-A")
      (footprint "eagle-import:B3B-XH")
      (libsource (lib "eagle-import") (part "03-JST-B3B-XH-A"))
    )
    (comp (ref "X13")
      (value "02-JST-B3B-XH-A")
      (footprint "eagle-import:B2B-XH")
      (libsource (lib "eagle-import") (part "02-JST-B3B-XH-A"))
    )
    (comp (ref "X14")
      (value "02-JST-B3B-XH-A")
      (footprint "eagle-import:B2B-XH")
      (libsource (lib "eagle-import") (part "02-JST-B3B-XH-A"))
    )
    (comp (ref "X15")
      (value "02-JST-B3B-XH-A")
      (footprint "eagle-import:B2B-XH")
      (libsource (lib "eagle-import") (part "02-JST-B3B-XH-A"))
    )
    (comp (ref "X16")
      (value "02-JST-B3B-XH-A")
      (footprint "eagle-import:B2B-XH")
      (libsource (lib "eagle-import") (part "02-JST-B3B-XH-A"))
    )
    (comp (ref "X17")
      (value "02-JST-B3B-XH-A")
      (footprint "eagle-import:B2B-XH")
      (libsource (lib "eagle-import") (part "02-JST-B3B-XH-A"))
    )
    (comp (ref "X18")
      (value "02-JST-B3B-XH-A")
      (footprint "eagle-import:B2B-XH")
      (libsource (lib "eagle-import") (part "02-JST-B3B-XH-A"))
    )
    (comp (ref "C50")
      (value "100n")
      (footprint "eagle-import:0603_CAP")
      (libsource (lib "eagle-import") (part "CAPACITOR0603_CAP"))
    )
    (comp (ref "C51")
      (value "10p")
      (footprint "eagle-import:0603_CAP")
      (libsource (lib "eagle-import") (part "CAPACITOR0603_CAP"))
    )
    (comp (ref "C52")
      (value "3.3n")
      (footprint "eagle-import:0603_CAP")
      (libsource (lib "eagle-import") (part "CAPACITOR0603_CAP"))
    )
    (comp (ref "C53")
      (value "1u")
      (footprint "eagle-import:0603_CAP")
      (libsource (lib "eagle-import") (part "CAPACITOR0603_CAP"))
    )
    (comp (ref "C54")
      (value "22uF")
      (footprint "eagle-import:1206_CAP")
      (libsource (lib "eagle-import") (part "CAPACITOR1206_CAP"))
    )
    (comp (ref "C55")
      (value "22uF")
      (footprint "eagle-import:0805_CAP")
      (libsource (lib "eagle-import") (part "CAPACITOR0805_CAP"))
    )
    (comp (ref "C56")
      (value "22uF")
      (footprint "eagle-import:0805_CAP")
      (libsource (lib "eagle-import") (part "CAPACITOR0805_CAP"))
    )
    (comp (ref "C57")
      (value "100n")
      (footprint "eagle-import:0603_CAP")
      (libsource (lib "eagle-import") (part "CAPACITOR0603_CAP"))
    )
    (comp (ref "C58")
      (value "10p")
      (footprint "eagle-import:0603_CAP")
      (libsource (lib "eagle-import") (part "CAPACITOR0603_CAP"))
    )
    (comp (ref "C59")
      (value "3.3n")
      (footprint "eagle-import:0603_CAP")
      (libsource (lib "eagle-import") (part "CAPACITOR0603_CAP"))
    )
    (comp (ref "C60")
      (value "1u")
      (footprint "eagle-import:0603_CAP")
      (libsource (lib "eagle-import") (part "CAPACITOR0603_CAP"))
    )
    (comp (ref "C61")
      (value "22uF")
      (footprint "eagle-import:1206_CAP")
      (libsource (lib "eagle-import") (part "CAPACITOR1206_CAP"))
    )
    (comp (ref "C62")
      (value "22uF")
      (footprint "eagle-import:0805_CAP")
      (libsource (lib "eagle-import") (part "CAPACITOR0805_CAP"))
    )
    (comp (ref "C63")
      (value "22uF")
      (footprint "eagle-import:0805_CAP")
      (libsource (lib "eagle-import") (part "CAPACITOR0805_CAP"))
    )
    (comp (ref "L1")
      (value "4.7uH")
      (footprint "eagle-import:IND_CR4")
      (libsource (lib "eagle-import") (part "INDUCTOR"))
    )
    (comp (ref "L2")
      (value "4.7uH")
      (footprint "eagle-import:IND_CR4")
      (libsource (lib "eagle-import") (part "INDUCTOR"))
    )
    (comp (ref "R33")
      (value "10k")
      (footprint "eagle-import:0603-RES")
      (libsource (lib "eagle-import") (part "RESISTOR0603_RES"))
    )
    (comp (ref "R34")
      (value "100k")
      (footprint "eagle-import:0603-RES")
      (libsource (lib "eagle-import") (part "RESISTOR0603_RES"))
    )
    (comp (ref "R35")
      (value "18k")
      (footprint "eagle-import:0603-RES")
      (libsource (lib "eagle-import") (part "RESISTOR0603_RES"))
    )
    (comp (ref "R36")
      (value "10k")
      (footprint "eagle-import:0603-RES")
      (libsource (lib "eagle-import") (part "RESISTOR0603_RES"))
    )
    (comp (ref "R37")
      (value "100k")
      (footprint "eagle-import:0603-RES")
      (libsource (lib "eagle-import") (part "RESISTOR0603_RES"))
    )
    (comp (ref "R38")
      (value "20k")
      (footprint "eagle-import:0603-RES")
      (libsource (lib "eagle-import") (part "RESISTOR0603_RES"))
    )
    (comp (ref "R39")
      (value "10K")
      (footprint "eagle-import:0603-RES")
      (libsource (lib "eagle-import") (part "RESISTOR0603_RES"))
    )
    (comp (ref "U3")
      (value "TPS54227DDAR")
      (footprint "eagle-import:TPS54227DDAR_VREG_LM5017MR_NOPB")
      (fields (field (name "MF") "Texas Instruments"))
      (libsource (lib "eagle-import") (part "TPS54227DDAR"))
    )
    (comp (ref "U5")
      (value "TPS54227DDAR")
      (footprint "eagle-import:TPS54227DDAR_VREG_LM5017MR_NOPB")
      (fields (field (name "MF") "Texas Instruments"))
      (libsource (lib "eagle-import") (part "TPS54227DDAR"))
    )
    (comp (ref "X22")
      (value "PIN_2X13.81MM_LONGPAD")
      (footprint "eagle-import:PIN_2X1_3.81MM_LONGPAD")
      (libsource (lib "eagle-import") (part "PIN_2X13.81MM_LONGPAD"))
    )
    (comp (ref "X23")
      (value "02-JST-B3B-XH-A")
      (footprint "eagle-import:B2B-XH")
      (libsource (lib "eagle-import") (part "02-JST-B3B-XH-A"))
    )
    (comp (ref "X24")
      (value "02-JST-B3B-XH-A")
      (footprint "eagle-import:B2B-XH")
      (libsource (lib "eagle-import") (part "02-JST-B3B-XH-A"))
    )
    (comp (ref "X29")
      (value "02-JST-B3B-XH-A")
      (footprint "eagle-import:B2B-XH")
      (libsource (lib "eagle-import") (part "02-JST-B3B-XH-A"))
    )
    (comp (ref "X30")
      (value "02-JST-B3B-XH-A")
      (footprint "eagle-import:B2B-XH")
      (libsource (lib "eagle-import") (part "02-JST-B3B-XH-A"))
    )
    (comp (ref "X31")
      (value "02-JST-B3B-XH-A")
      (footprint "eagle-import:B2B-XH")
      (libsource (lib "eagle-import") (part "02-JST-B3B-XH-A"))
    )
    (comp (ref "X32")
      (value "02-JST-B3B-XH-A")
      (footprint "eagle-import:B2B-XH")
      (libsource (lib "eagle-import") (part "02-JST-B3B-XH-A"))
    )
  )
  (nets
    (net (code "1") (name "+3V3") (class "Default")
      (node (ref "C10") (pin "1") (pinfunction "1_1") (pintype "bidirectional"))
      (node (ref "C12") (pin "1") (pinfunction "1_1") (pintype "bidirectional"))
      (node (ref "C14") (pin "1") (pinfunction "1_1") (pintype "bidirectional"))
      (node (ref "C17") (pin "1") (pinfunction "1_1") (pintype "bidirectional"))
      (node (ref "C2") (pin "1") (pinfunction "1_1") (pintype "bidirectional"))
      (node (ref "C21") (pin "1") (pinfunction "1_1") (pintype "bidirectional"))
      (node (ref "C3") (pin "1") (pinfunction "1_1") (pintype "bidirectional"))
      (node (ref "C33") (pin "1") (pinfunction "1_1") (pintype "bidirectional"))
      (node (ref "C44") (pin "1") (pinfunction "1_1") (pintype "bidirectional"))
      (node (ref "C45") (pin "1") (pinfunction "1_1") (pintype "bidirectional"))
      (node (ref "C46") (pin "1") (pinfunction "1_1") (pintype "bidirectional"))
      (node (ref "C47") (pin "P$1") (pinfunction "1_P$1") (pintype "bidirectional"))
      (node (ref "C48") (pin "1") (pinfunction "1_1") (pintype "bidirectional"))
      (node (ref "C49") (pin "1") (pinfunction "1_1") (pintype "bidirectional"))
      (node (ref "C58") (pin "1") (pinfunction "1_1") (pintype "bidirectional"))
      (node (ref "C6") (pin "1") (pinfunction "1_1") (pintype "bidirectional"))
      (node (ref "C62") (pin "P$1") (pinfunction "1_P$1") (pintype "bidirectional"))
      (node (ref "C63") (pin "P$1") (pinfunction "1_P$1") (pintype "bidirectional"))
      (node (ref "C7") (pin "1") (pinfunction "1_1") (pintype "bidirectional"))
      (node (ref "C8") (pin "1") (pinfunction "1_1") (pintype "bidirectional"))
      (node (ref "L2") (pin "P$2") (pinfunction "2_P$2") (pintype "passive"))
      (node (ref "R11") (pin "1") (pinfunction "1_1") (pintype "passive"))
      (node (ref "R13") (pin "1") (pinfunction "1_1") (pintype "passive"))
      (node (ref "R15") (pin "1") (pinfunction "1_1") (pintype "passive"))
      (node (ref "R16") (pin "1") (pinfunction "1_1") (pintype "passive"))
      (node (ref "R29") (pin "1") (pinfunction "1_1") (pintype "passive"))
      (node (ref "R31") (pin "1") (pinfunction "1_1") (pintype "passive"))
      (node (ref "R32") (pin "1") (pinfunction "1_1") (pintype "passive"))
      (node (ref "R37") (pin "2") (pinfunction "2_2") (pintype "passive"))
      (node (ref "R4") (pin "1") (pinfunction "1_1") (pintype "passive"))
      (node (ref "R7") (pin "1") (pinfunction "1_1") (pintype "passive"))
      (node (ref "R9") (pin "1") (pinfunction "1_1") (pintype "passive"))
      (node (ref "U$2") (pin "VDD") (pinfunction "VDD_VDD") (pintype "power_in"))
      (node (ref "U$3") (pin "VDD") (pinfunction "VDD_VDD") (pintype "power_in"))
      (node (ref "U$4") (pin "VDD") (pinfunction "VDD_VDD") (pintype "power_in"))
      (node (ref "U$5") (pin "VDD") (pinfunction "VDD_VDD") (pintype "power_in"))
      (node (ref "U$6") (pin "VDD") (pinfunction "VDD_VDD") (pintype "power_in"))
      (node (ref "U$7") (pin "VDD") (pinfunction "VDD_VDD") (pintype "power_in"))
      (node (ref "U$8") (pin "VDD") (pinfunction "VDD_VDD") (pintype "power_in"))
      (node (ref "U$9") (pin "VDD") (pinfunction "VDD_VDD") (pintype "power_in"))
      (node (ref "U1") (pin "100") (pinfunction "VDD_100") (pintype "power_in"))
      (node (ref "U1") (pin "11") (pinfunction "VDD_2_11") (pintype "power_in"))
      (node (ref "U1") (pin "19") (pinfunction "VDD_3_19") (pintype "power_in"))
      (node (ref "U1") (pin "21") (pinfunction "VREF+_21") (pintype "power_in"))
      (node (ref "U1") (pin "22") (pinfunction "VDDA_22") (pintype "power_in"))
      (node (ref "U1") (pin "28") (pinfunction "VDD_4_28") (pintype "power_in"))
      (node (ref "U1") (pin "50") (pinfunction "VDD_5_50") (pintype "power_in"))
      (node (ref "U1") (pin "6") (pinfunction "VBAT_6") (pintype "power_in"))
      (node (ref "U1") (pin "75") (pinfunction "VDD_6_75") (pintype "power_in"))
      (node (ref "X10") (pin "P$3") (pinfunction "1_P$3") (pintype "passive"))
      (node (ref "X11") (pin "P$3") (pinfunction "1_P$3") (pintype "passive"))
      (node (ref "X12") (pin "P$3") (pinfunction "1_P$3") (pintype "passive"))
      (node (ref "X26") (pin "P$1") (pinfunction "1_P$1") (pintype "passive"))
      (node (ref "X29") (pin "P$2") (pinfunction "1_P$2") (pintype "passive"))
      (node (ref "X30") (pin "P$2") (pinfunction "1_P$2") (pintype "passive"))
      (node (ref "X7") (pin "P$3") (pinfunction "1_P$3") (pintype "passive"))
      (node (ref "X8") (pin "P$3") (pinfunction "1_P$3") (pintype "passive"))
      (node (ref "X9") (pin "P$3") (pinfunction "1_P$3") (pintype "passive"))
    )
    (net (code "2") (name "+5V") (class "Default")
      (node (ref "C35") (pin "P$2") (pinfunction "2_P$2") (pintype "bidirectional"))
      (node (ref "C37") (pin "1") (pinfunction "1_1") (pintype "bidirectional"))
      (node (ref "C38") (pin "1") (pinfunction "1_1") (pintype "bidirectional"))
      (node (ref "C40") (pin "2") (pinfunction "2_2") (pintype "bidirectional"))
      (node (ref "C42") (pin "1") (pinfunction "1_1") (pintype "bidirectional"))
      (node (ref "C5") (pin "2") (pinfunction "2_2") (pintype "bidirectional"))
      (node (ref "C51") (pin "1") (pinfunction "1_1") (pintype "bidirectional"))
      (node (ref "C55") (pin "P$1") (pinfunction "1_P$1") (pintype "bidirectional"))
      (node (ref "C56") (pin "P$1") (pinfunction "1_P$1") (pintype "bidirectional"))
      (node (ref "D10") (pin "2") (pinfunction "2_2") (pintype "bidirectional"))
      (node (ref "D2") (pin "K") (pinfunction "CATHODE_K") (pintype "bidirectional"))
      (node (ref "D3") (pin "1") (pinfunction "1_1") (pintype "bidirectional"))
      (node (ref "J3") (pin "VCC") (pinfunction "VCC_VCC") (pintype "bidirectional"))
      (node (ref "J3C") (pin "VCC") (pinfunction "VCC_VCC") (pintype "bidirectional"))
      (node (ref "J3C1") (pin "VCC") (pinfunction "VCC_VCC") (pintype "bidirectional"))
      (node (ref "L1") (pin "P$2") (pinfunction "2_P$2") (pintype "passive"))
      (node (ref "R34") (pin "2") (pinfunction "2_2") (pintype "passive"))
      (node (ref "U2") (pin "16") (pinfunction "VCC_16") (pintype "bidirectional"))
      (node (ref "U4") (pin "11") (pinfunction "VCC5V_11") (pintype "bidirectional"))
      (node (ref "X14") (pin "P$2") (pinfunction "1_P$2") (pintype "passive"))
      (node (ref "X19") (pin "P$4") (pinfunction "1_P$4") (pintype "passive"))
      (node (ref "X20") (pin "P$4") (pinfunction "1_P$4") (pintype "passive"))
      (node (ref "X31") (pin "P$2") (pinfunction "1_P$2") (pintype "passive"))
      (node (ref "X32") (pin "P$2") (pinfunction "1_P$2") (pintype "passive"))
    )
    (net (code "3") (name "+12V") (class "Default")
      (node (ref "C11") (pin "+") (pinfunction "+_+") (pintype "passive"))
      (node (ref "C13") (pin "+") (pinfunction "+_+") (pintype "passive"))
      (node (ref "C15") (pin "+") (pinfunction "+_+") (pintype "passive"))
      (node (ref "C20") (pin "+") (pinfunction "+_+") (pintype "passive"))
      (node (ref "C22") (pin "+") (pinfunction "+_+") (pintype "passive"))
      (node (ref "C32") (pin "+") (pinfunction "+_+") (pintype "passive"))
      (node (ref "C34") (pin "+") (pinfunction "+_+") (pintype "passive"))
      (node (ref "C54") (pin "1") (pinfunction "1_1") (pintype "bidirectional"))
      (node (ref "C61") (pin "1") (pinfunction "1_1") (pintype "bidirectional"))
      (node (ref "C9") (pin "+") (pinfunction "+_+") (pintype "passive"))
      (node (ref "D1") (pin "1") (pinfunction "1_1") (pintype "bidirectional"))
      (node (ref "D11") (pin "1") (pinfunction "1_1") (pintype "bidirectional"))
      (node (ref "D13") (pin "K") (pinfunction "CATHODE_K") (pintype "bidirectional"))
      (node (ref "D14") (pin "K") (pinfunction "CATHODE_K") (pintype "bidirectional"))
      (node (ref "D15") (pin "1") (pinfunction "1_1") (pintype "bidirectional"))
      (node (ref "D5") (pin "K") (pinfunction "CATHODE_K") (pintype "bidirectional"))
      (node (ref "D6") (pin "1") (pinfunction "1_1") (pintype "bidirectional"))
      (node (ref "D7") (pin "K") (pinfunction "CATHODE_K") (pintype "bidirectional"))
      (node (ref "D8") (pin "1") (pinfunction "1_1") (pintype "bidirectional"))
      (node (ref "D9") (pin "K") (pinfunction "CATHODE_K") (pintype "bidirectional"))
      (node (ref "R33") (pin "1") (pinfunction "1_1") (pintype "passive"))
      (node (ref "R36") (pin "1") (pinfunction "1_1") (pintype "passive"))
      (node (ref "U$2") (pin "VMOT") (pinfunction "VMOT_VMOT") (pintype "power_in"))
      (node (ref "U$3") (pin "VMOT") (pinfunction "VMOT_VMOT") (pintype "power_in"))
      (node (ref "U$4") (pin "VMOT") (pinfunction "VMOT_VMOT") (pintype "power_in"))
      (node (ref "U$5") (pin "VMOT") (pinfunction "VMOT_VMOT") (pintype "power_in"))
      (node (ref "U$6") (pin "VMOT") (pinfunction "VMOT_VMOT") (pintype "power_in"))
      (node (ref "U$7") (pin "VMOT") (pinfunction "VMOT_VMOT") (pintype "power_in"))
      (node (ref "U$8") (pin "VMOT") (pinfunction "VMOT_VMOT") (pintype "power_in"))
      (node (ref "U$9") (pin "VMOT") (pinfunction "VMOT_VMOT") (pintype "power_in"))
      (node (ref "U3") (pin "8") (pinfunction "VIN_8") (pintype "input"))
      (node (ref "U5") (pin "8") (pinfunction "VIN_8") (pintype "input"))
      (node (ref "X13") (pin "P$2") (pinfunction "1_P$2") (pintype "passive"))
      (node (ref "X15") (pin "P$2") (pinfunction "1_P$2") (pintype "passive"))
      (node (ref "X16") (pin "P$2") (pinfunction "1_P$2") (pintype "passive"))
      (node (ref "X17") (pin "P$2") (pinfunction "1_P$2") (pintype "passive"))
      (node (ref "X18") (pin "P$2") (pinfunction "1_P$2") (pintype "passive"))
      (node (ref "X22") (pin "1") (pinfunction "1_1") (pintype "bidirectional"))
      (node (ref "X23") (pin "P$2") (pinfunction "1_P$2") (pintype "passive"))
      (node (ref "X24") (pin "P$2") (pinfunction "1_P$2") (pintype "passive"))
    )
    (net (code "4") (name "D0_N") (class "Default")
      (node (ref "D16") (pin "2") (pinfunction "2_2") (pintype "bidirectional"))
      (node (ref "J1") (pin "2") (pinfunction "D-_2") (pintype "bidirectional"))
      (node (ref "U4") (pin "9") (pinfunction "UDM_9") (pintype "bidirectional"))
    )
    (net (code "5") (name "D0_P") (class "Default")
      (node (ref "D16") (pin "1") (pinfunction "1_1") (pintype "bidirectional"))
      (node (ref "J1") (pin "3") (pinfunction "D+_3") (pintype "bidirectional"))
      (node (ref "U4") (pin "10") (pinfunction "UDP_10") (pintype "bidirectional"))
    )
    (net (code "6") (name "D1_N") (class "Default")
      (node (ref "U2") (pin "6") (pinfunction "UD-_6") (pintype "bidirectional"))
      (node (ref "U4") (pin "7") (pinfunction "DM1_7") (pintype "bidirectional"))
    )
    (net (code "7") (name "D1_P") (class "Default")
      (node (ref "U2") (pin "5") (pinfunction "UD+_5") (pintype "bidirectional"))
      (node (ref "U4") (pin "8") (pinfunction "DP1_8") (pintype "bidirectional"))
    )
    (net (code "8") (name "D2_N") (class "Default")
      (node (ref "J3") (pin "D-") (pinfunction "D-_D-") (pintype "bidirectional"))
      (node (ref "U4") (pin "5") (pinfunction "DM2_5") (pintype "bidirectional"))
    )
    (net (code "9") (name "D2_P") (class "Default")
      (node (ref "J3") (pin "D+") (pinfunction "D+_D+") (pintype "bidirectional"))
      (node (ref "U4") (pin "6") (pinfunction "DP2_6") (pintype "bidirectional"))
    )
    (net (code "10") (name "D3_N") (class "Default")
      (node (ref "J3C") (pin "D-") (pinfunction "D-_D-") (pintype "bidirectional"))
      (node (ref "U4") (pin "3") (pinfunction "DM3_3") (pintype "bidirectional"))
    )
    (net (code "11") (name "D3_P") (class "Default")
      (node (ref "J3C") (pin "D+") (pinfunction "D+_D+") (pintype "bidirectional"))
      (node (ref "U4") (pin "4") (pinfunction "DP3_4") (pintype "bidirectional"))
    )
    (net (code "12") (name "D4_N") (class "Default")
      (node (ref "J3C1") (pin "D-") (pinfunction "D-_D-") (pintype "bidirectional"))
      (node (ref "U4") (pin "1") (pinfunction "DM4_1") (pintype "bidirectional"))
    )
    (net (code "13") (name "D4_P") (class "Default")
      (node (ref "J3C1") (pin "D+") (pinfunction "D+_D+") (pintype "bidirectional"))
      (node (ref "U4") (pin "2") (pinfunction "DP4_2") (pintype "bidirectional"))
    )
    (net (code "14") (name "DTR") (class "Default")
      (node (ref "R3") (pin "2") (pinfunction "2_2") (pintype "passive"))
      (node (ref "U1") (pin "70") (pinfunction "PA11_70") (pintype "bidirectional"))
    )
    (net (code "15") (name "GND") (class "Default")
      (node (ref "C1") (pin "P$2") (pinfunction "2_P$2") (pintype "bidirectional"))
      (node (ref "C10") (pin "2") (pinfunction "2_2") (pintype "bidirectional"))
      (node (ref "C11") (pin "-") (pinfunction "-_-") (pintype "passive"))
      (node (ref "C12") (pin "2") (pinfunction "2_2") (pintype "bidirectional"))
      (node (ref "C13") (pin "-") (pinfunction "-_-") (pintype "passive"))
      (node (ref "C14") (pin "2") (pinfunction "2_2") (pintype "bidirectional"))
      (node (ref "C15") (pin "-") (pinfunction "-_-") (pintype "passive"))
      (node (ref "C16") (pin "1") (pinfunction "1_1") (pintype "bidirectional"))
      (node (ref "C17") (pin "2") (pinfunction "2_2") (pintype "bidirectional"))
      (node (ref "C18") (pin "1") (pinfunction "1_1") (pintype "bidirectional"))
      (node (ref "C19") (pin "1") (pinfunction "1_1") (pintype "bidirectional"))
      (node (ref "C2") (pin "2") (pinfunction "2_2") (pintype "bidirectional"))
      (node (ref "C20") (pin "-") (pinfunction "-_-") (pintype "passive"))
      (node (ref "C21") (pin "2") (pinfunction "2_2") (pintype "bidirectional"))
      (node (ref "C22") (pin "-") (pinfunction "-_-") (pintype "passive"))
      (node (ref "C23") (pin "2") (pinfunction "2_2") (pintype "bidirectional"))
      (node (ref "C24") (pin "2") (pinfunction "2_2") (pintype "bidirectional"))
      (node (ref "C25") (pin "2") (pinfunction "2_2") (pintype "bidirectional"))
      (node (ref "C26") (pin "2") (pinfunction "2_2") (pintype "bidirectional"))
      (node (ref "C27") (pin "2") (pinfunction "2_2") (pintype "bidirectional"))
      (node (ref "C28") (pin "2") (pinfunction "2_2") (pintype "bidirectional"))
      (node (ref "C29") (pin "2") (pinfunction "2_2") (pintype "bidirectional"))
      (node (ref "C3") (pin "2") (pinfunction "2_2") (pintype "bidirectional"))
      (node (ref "C30") (pin "2") (pinfunction "2_2") (pintype "bidirectional"))
      (node (ref "C31") (pin "2") (pinfunction "2_2") (pintype "bidirectional"))
      (node (ref "C32") (pin "-") (pinfunction "-_-") (pintype "passive"))
      (node (ref "C33") (pin "2") (pinfunction "2_2") (pintype "bidirectional"))
      (node (ref "C34") (pin "-") (pinfunction "-_-") (pintype "passive"))
      (node (ref "C35") (pin "P$1") (pinfunction "1_P$1") (pintype "bidirectional"))
      (node (ref "C36") (pin "P$1") (pinfunction "1_P$1") (pintype "bidirectional"))
      (node (ref "C37") (pin "2") (pinfunction "2_2") (pintype "bidirectional"))
      (node (ref "C38") (pin "2") (pinfunction "2_2") (pintype "bidirectional"))
      (node (ref "C39") (pin "P$1") (pinfunction "1_P$1") (pintype "bidirectional"))
      (node (ref "C4") (pin "2") (pinfunction "2_2") (pintype "bidirectional"))
      (node (ref "C40") (pin "1") (pinfunction "1_1") (pintype "bidirectional"))
      (node (ref "C41") (pin "2") (pinfunction "2_2") (pintype "bidirectional"))
      (node (ref "C42") (pin "2") (pinfunction "2_2") (pintype "bidirectional"))
      (node (ref "C43") (pin "2") (pinfunction "2_2") (pintype "bidirectional"))
      (node (ref "C44") (pin "2") (pinfunction "2_2") (pintype "bidirectional"))
      (node (ref "C45") (pin "2") (pinfunction "2_2") (pintype "bidirectional"))
      (node (ref "C46") (pin "2") (pinfunction "2_2") (pintype "bidirectional"))
      (node (ref "C47") (pin "P$2") (pinfunction "2_P$2") (pintype "bidirectional"))
      (node (ref "C48") (pin "2") (pinfunction "2_2") (pintype "bidirectional"))
      (node (ref "C49") (pin "2") (pinfunction "2_2") (pintype "bidirectional"))
      (node (ref "C5") (pin "1") (pinfunction "1_1") (pintype "bidirectional"))
      (node (ref "C52") (pin "2") (pinfunction "2_2") (pintype "bidirectional"))
      (node (ref "C53") (pin "2") (pinfunction "2_2") (pintype "bidirectional"))
      (node (ref "C54") (pin "2") (pinfunction "2_2") (pintype "bidirectional"))
      (node (ref "C55") (pin "P$2") (pinfunction "2_P$2") (pintype "bidirectional"))
      (node (ref "C56") (pin "P$2") (pinfunction "2_P$2") (pintype "bidirectional"))
      (node (ref "C59") (pin "2") (pinfunction "2_2") (pintype "bidirectional"))
      (node (ref "C6") (pin "2") (pinfunction "2_2") (pintype "bidirectional"))
      (node (ref "C60") (pin "2") (pinfunction "2_2") (pintype "bidirectional"))
      (node (ref "C61") (pin "2") (pinfunction "2_2") (pintype "bidirectional"))
      (node (ref "C62") (pin "P$2") (pinfunction "2_P$2") (pintype "bidirectional"))
      (node (ref "C63") (pin "P$2") (pinfunction "2_P$2") (pintype "bidirectional"))
      (node (ref "C7") (pin "2") (pinfunction "2_2") (pintype "bidirectional"))
      (node (ref "C8") (pin "2") (pinfunction "2_2") (pintype "bidirectional"))
      (node (ref "C9") (pin "-") (pinfunction "-_-") (pintype "passive"))
      (node (ref "D16") (pin "3") (pinfunction "3_3") (pintype "bidirectional"))
      (node (ref "J1") (pin "5") (pinfunction "GND_5") (pintype "bidirectional"))
      (node (ref "J1") (pin "GND1") (pinfunction "GND_GND1") (pintype "bidirectional"))
      (node (ref "J1") (pin "GND2") (pinfunction "GND_GND2") (pintype "bidirectional"))
      (node (ref "J1") (pin "GND3") (pinfunction "GND_GND3") (pintype "bidirectional"))
      (node (ref "J1") (pin "GND4") (pinfunction "GND_GND4") (pintype "bidirectional"))
      (node (ref "J3") (pin "COM1") (pinfunction "COM_COM1") (pintype "bidirectional"))
      (node (ref "J3") (pin "COM2") (pinfunction "COM_COM2") (pintype "bidirectional"))
      (node (ref "J3") (pin "GND") (pinfunction "GND_GND") (pintype "bidirectional"))
      (node (ref "J3C") (pin "COM1") (pinfunction "COM_COM1") (pintype "bidirectional"))
      (node (ref "J3C") (pin "COM2") (pinfunction "COM_COM2") (pintype "bidirectional"))
      (node (ref "J3C") (pin "GND") (pinfunction "GND_GND") (pintype "bidirectional"))
      (node (ref "J3C1") (pin "COM1") (pinfunction "COM_COM1") (pintype "bidirectional"))
      (node (ref "J3C1") (pin "COM2") (pinfunction "COM_COM2") (pintype "bidirectional"))
      (node (ref "J3C1") (pin "GND") (pinfunction "GND_GND") (pintype "bidirectional"))
      (node (ref "R17") (pin "1") (pinfunction "1_1") (pintype "passive"))
      (node (ref "R19") (pin "1") (pinfunction "1_1") (pintype "passive"))
      (node (ref "R21") (pin "1") (pinfunction "1_1") (pintype "passive"))
      (node (ref "R23") (pin "1") (pinfunction "1_1") (pintype "passive"))
      (node (ref "R25") (pin "1") (pinfunction "1_1") (pintype "passive"))
      (node (ref "R27") (pin "1") (pinfunction "1_1") (pintype "passive"))
      (node (ref "R30") (pin "2") (pinfunction "2_2") (pintype "passive"))
      (node (ref "R35") (pin "1") (pinfunction "1_1") (pintype "passive"))
      (node (ref "R39") (pin "2") (pinfunction "2_2") (pintype "passive"))
      (node (ref "S1") (pin "2A") (pinfunction "3_2A") (pintype "bidirectional"))
      (node (ref "S1") (pin "2B") (pinfunction "4_2B") (pintype "bidirectional"))
      (node (ref "U$2") (pin "GND") (pinfunction "GND_GND") (pintype "power_in"))
      (node (ref "U$2") (pin "GND@0") (pinfunction "GND_GND@0") (pintype "power_in"))
      (node (ref "U$21") (pin "S1") (pinfunction "S_S1") (pintype "bidirectional"))
      (node (ref "U$21") (pin "S2") (pinfunction "S_S2") (pintype "bidirectional"))
      (node (ref "U$21") (pin "S3") (pinfunction "S_S3") (pintype "bidirectional"))
      (node (ref "U$22") (pin "S1") (pinfunction "S_S1") (pintype "bidirectional"))
      (node (ref "U$22") (pin "S2") (pinfunction "S_S2") (pintype "bidirectional"))
      (node (ref "U$22") (pin "S3") (pinfunction "S_S3") (pintype "bidirectional"))
      (node (ref "U$23") (pin "S1") (pinfunction "S_S1") (pintype "bidirectional"))
      (node (ref "U$23") (pin "S2") (pinfunction "S_S2") (pintype "bidirectional"))
      (node (ref "U$23") (pin "S3") (pinfunction "S_S3") (pintype "bidirectional"))
      (node (ref "U$24") (pin "S1") (pinfunction "S_S1") (pintype "bidirectional"))
      (node (ref "U$24") (pin "S2") (pinfunction "S_S2") (pintype "bidirectional"))
      (node (ref "U$24") (pin "S3") (pinfunction "S_S3") (pintype "bidirectional"))
      (node (ref "U$25") (pin "S1") (pinfunction "S_S1") (pintype "bidirectional"))
      (node (ref "U$25") (pin "S2") (pinfunction "S_S2") (pintype "bidirectional"))
      (node (ref "U$25") (pin "S3") (pinfunction "S_S3") (pintype "bidirectional"))
      (node (ref "U$26") (pin "S1") (pinfunction "S_S1") (pintype "bidirectional"))
      (node (ref "U$26") (pin "S2") (pinfunction "S_S2") (pintype "bidirectional"))
      (node (ref "U$26") (pin "S3") (pinfunction "S_S3") (pintype "bidirectional"))
      (node (ref "U$3") (pin "GND") (pinfunction "GND_GND") (pintype "power_in"))
      (node (ref "U$3") (pin "GND@0") (pinfunction "GND_GND@0") (pintype "power_in"))
      (node (ref "U$4") (pin "GND") (pinfunction "GND_GND") (pintype "power_in"))
      (node (ref "U$4") (pin "GND@0") (pinfunction "GND_GND@0") (pintype "power_in"))
      (node (ref "U$5") (pin "GND") (pinfunction "GND_GND") (pintype "power_in"))
      (node (ref "U$5") (pin "GND@0") (pinfunction "GND_GND@0") (pintype "power_in"))
      (node (ref "U$6") (pin "GND") (pinfunction "GND_GND") (pintype "power_in"))
      (node (ref "U$6") (pin "GND@0") (pinfunction "GND_GND@0") (pintype "power_in"))
      (node (ref "U$7") (pin "GND") (pinfunction "GND_GND") (pintype "power_in"))
      (node (ref "U$7") (pin "GND@0") (pinfunction "GND_GND@0") (pintype "power_in"))
      (node (ref "U$8") (pin "GND") (pinfunction "GND_GND") (pintype "power_in"))
      (node (ref "U$8") (pin "GND@0") (pinfunction "GND_GND@0") (pintype "power_in"))
      (node (ref "U$9") (pin "GND") (pinfunction "GND_GND") (pintype "power_in"))
      (node (ref "U$9") (pin "GND@0") (pinfunction "GND_GND@0") (pintype "power_in"))
      (node (ref "U1") (pin "10") (pinfunction "VSS_2_10") (pintype "power_in"))
      (node (ref "U1") (pin "20") (pinfunction "VSSA/VREF-_20") (pintype "power_in"))
      (node (ref "U1") (pin "27") (pinfunction "VSS_3_27") (pintype "power_in"))
      (node (ref "U1") (pin "49") (pinfunction "VSS_4_49") (pintype "power_in"))
      (node (ref "U1") (pin "74") (pinfunction "VSS_5_74") (pintype "power_in"))
      (node (ref "U1") (pin "99") (pinfunction "VSS_99") (pintype "power_in"))
      (node (ref "U2") (pin "1") (pinfunction "GND_1") (pintype "bidirectional"))
      (node (ref "U3") (pin "5") (pinfunction "GND_5") (pintype "power_in"))
      (node (ref "U3") (pin "9") (pinfunction "GND_9") (pintype "power_in"))
      (node (ref "U4") (pin "12") (pinfunction "GND_12") (pintype "bidirectional"))
      (node (ref "U5") (pin "5") (pinfunction "GND_5") (pintype "power_in"))
      (node (ref "U5") (pin "9") (pinfunction "GND_9") (pintype "power_in"))
      (node (ref "X10") (pin "P$2") (pinfunction "1_P$2") (pintype "passive"))
      (node (ref "X11") (pin "P$2") (pinfunction "1_P$2") (pintype "passive"))
      (node (ref "X12") (pin "P$2") (pinfunction "1_P$2") (pintype "passive"))
      (node (ref "X19") (pin "P$5") (pinfunction "1_P$5") (pintype "passive"))
      (node (ref "X20") (pin "P$5") (pinfunction "1_P$5") (pintype "passive"))
      (node (ref "X21") (pin "P$4") (pinfunction "1_P$4") (pintype "passive"))
      (node (ref "X22") (pin "2") (pinfunction "2_2") (pintype "bidirectional"))
      (node (ref "X23") (pin "P$1") (pinfunction "1_P$1") (pintype "passive"))
      (node (ref "X24") (pin "P$1") (pinfunction "1_P$1") (pintype "passive"))
      (node (ref "X26") (pin "P$5") (pinfunction "1_P$5") (pintype "passive"))
      (node (ref "X27") (pin "P$5") (pinfunction "1_P$5") (pintype "passive"))
      (node (ref "X28") (pin "P$5") (pinfunction "1_P$5") (pintype "passive"))
      (node (ref "X29") (pin "P$1") (pinfunction "1_P$1") (pintype "passive"))
      (node (ref "X30") (pin "P$1") (pinfunction "1_P$1") (pintype "passive"))
      (node (ref "X31") (pin "P$1") (pinfunction "1_P$1") (pintype "passive"))
      (node (ref "X32") (pin "P$1") (pinfunction "1_P$1") (pintype "passive"))
      (node (ref "X7") (pin "P$2") (pinfunction "1_P$2") (pintype "passive"))
      (node (ref "X8") (pin "P$2") (pinfunction "1_P$2") (pintype "passive"))
      (node (ref "X9") (pin "P$2") (pinfunction "1_P$2") (pintype "passive"))
      (node (ref "Y1") (pin "2_GND") (pinfunction "2_2_GND") (pintype "bidirectional"))
      (node (ref "Y1") (pin "4_GND") (pinfunction "2_4_GND") (pintype "bidirectional"))
      (node (ref "Y2") (pin "2_GND") (pinfunction "2_2_GND") (pintype "bidirectional"))
      (node (ref "Y2") (pin "4_GND") (pinfunction "2_4_GND") (pintype "bidirectional"))
      (node (ref "Y3") (pin "2_GND") (pinfunction "2_2_GND") (pintype "bidirectional"))
      (node (ref "Y3") (pin "4_GND") (pinfunction "2_4_GND") (pintype "bidirectional"))
    )
    (net (code "16") (name "INPUT_RESERVED_1") (class "Default")
      (node (ref "C27") (pin "1") (pinfunction "1_1") (pintype "bidirectional"))
      (node (ref "R12") (pin "2") (pinfunction "2_2") (pintype "passive"))
      (node (ref "U1") (pin "45") (pinfunction "PE14_45") (pintype "bidirectional"))
    )
    (net (code "17") (name "INPUT_RESERVED_2") (class "Default")
      (node (ref "C28") (pin "1") (pinfunction "1_1") (pintype "bidirectional"))
      (node (ref "R14") (pin "2") (pinfunction "2_2") (pintype "passive"))
      (node (ref "U1") (pin "44") (pinfunction "PE13_44") (pintype "bidirectional"))
    )
    (net (code "18") (name "INPUT_X_END") (class "Default")
      (node (ref "C23") (pin "1") (pinfunction "1_1") (pintype "bidirectional"))
      (node (ref "R5") (pin "2") (pinfunction "2_2") (pintype "passive"))
      (node (ref "U1") (pin "57") (pinfunction "PD10_57") (pintype "bidirectional"))
    )
    (net (code "19") (name "INPUT_Y_END1") (class "Default")
      (node (ref "C24") (pin "1") (pinfunction "1_1") (pintype "bidirectional"))
      (node (ref "R6") (pin "2") (pinfunction "2_2") (pintype "passive"))
      (node (ref "U1") (pin "56") (pinfunction "PD9_56") (pintype "bidirectional"))
    )
    (net (code "20") (name "INPUT_Y_END2") (class "Default")
      (node (ref "C25") (pin "1") (pinfunction "1_1") (pintype "bidirectional"))
      (node (ref "R8") (pin "2") (pinfunction "2_2") (pintype "passive"))
      (node (ref "U1") (pin "55") (pinfunction "PD8_55") (pintype "bidirectional"))
    )
    (net (code "21") (name "INPUT_Z_END") (class "Default")
      (node (ref "C26") (pin "1") (pinfunction "1_1") (pintype "bidirectional"))
      (node (ref "R10") (pin "2") (pinfunction "2_2") (pintype "passive"))
      (node (ref "U1") (pin "46") (pinfunction "PE15_46") (pintype "bidirectional"))
    )
    (net (code "22") (name "MOT_A_DIR") (class "Default")
      (node (ref "U$7") (pin "DIR") (pinfunction "DIR_DIR") (pintype "input"))
      (node (ref "U1") (pin "82") (pinfunction "PD1_82") (pintype "bidirectional"))
    )
    (net (code "23") (name "MOT_A_EN") (class "Default")
      (node (ref "U$7") (pin "EN") (pinfunction "EN_EN") (pintype "input"))
      (node (ref "U1") (pin "84") (pinfunction "PD3_84") (pintype "bidirectional"))
    )
    (net (code "24") (name "MOT_A_STEP") (class "Default")
      (node (ref "U$7") (pin "STEP") (pinfunction "STEP_STEP") (pintype "input"))
      (node (ref "U1") (pin "83") (pinfunction "PD2_83") (pintype "bidirectional"))
    )
    (net (code "25") (name "MOT_B_DIR") (class "Default")
      (node (ref "U$8") (pin "DIR") (pinfunction "DIR_DIR") (pintype "input"))
      (node (ref "U1") (pin "64") (pinfunction "PC7_64") (pintype "bidirectional"))
    )
    (net (code "26") (name "MOT_B_EN") (class "Default")
      (node (ref "U$8") (pin "EN") (pinfunction "EN_EN") (pintype "input"))
      (node (ref "U1") (pin "66") (pinfunction "PC9_66") (pintype "bidirectional"))
    )
    (net (code "27") (name "MOT_B_STEP") (class "Default")
      (node (ref "U$8") (pin "STEP") (pinfunction "STEP_STEP") (pintype "input"))
      (node (ref "U1") (pin "65") (pinfunction "PC8_65") (pintype "bidirectional"))
    )
    (net (code "28") (name "MOT_C_DIR") (class "Default")
      (node (ref "U$9") (pin "DIR") (pinfunction "DIR_DIR") (pintype "input"))
      (node (ref "U1") (pin "79") (pinfunction "PC11_79") (pintype "bidirectional"))
    )
    (net (code "29") (name "MOT_C_EN") (class "Default")
      (node (ref "U$9") (pin "EN") (pinfunction "EN_EN") (pintype "input"))
      (node (ref "U1") (pin "81") (pinfunction "PD0_81") (pintype "bidirectional"))
    )
    (net (code "30") (name "MOT_C_STEP") (class "Default")
      (node (ref "U$9") (pin "STEP") (pinfunction "STEP_STEP") (pintype "input"))
      (node (ref "U1") (pin "80") (pinfunction "PC12_80") (pintype "bidirectional"))
    )
    (net (code "31") (name "MOT_E_DIR") (class "Default")
      (node (ref "U$6") (pin "DIR") (pinfunction "DIR_DIR") (pintype "input"))
      (node (ref "U1") (pin "85") (pinfunction "PD4_85") (pintype "bidirectional"))
    )
    (net (code "32") (name "MOT_E_EN") (class "Default")
      (node (ref "U$6") (pin "EN") (pinfunction "EN_EN") (pintype "input"))
      (node (ref "U1") (pin "87") (pinfunction "PD6_87") (pintype "bidirectional"))
    )
    (net (code "33") (name "MOT_E_STEP") (class "Default")
      (node (ref "U$6") (pin "STEP") (pinfunction "STEP_STEP") (pintype "input"))
      (node (ref "U1") (pin "86") (pinfunction "PD5_86") (pintype "bidirectional"))
    )
    (net (code "34") (name "MOT_X_DIR") (class "Default")
      (node (ref "U$2") (pin "DIR") (pinfunction "DIR_DIR") (pintype "input"))
      (node (ref "U1") (pin "3") (pinfunction "PE4_3") (pintype "bidirectional"))
    )
    (net (code "35") (name "MOT_X_EN") (class "Default")
      (node (ref "U$2") (pin "EN") (pinfunction "EN_EN") (pintype "input"))
      (node (ref "U1") (pin "5") (pinfunction "PE6_5") (pintype "bidirectional"))
    )
    (net (code "36") (name "MOT_X_STEP") (class "Default")
      (node (ref "U$2") (pin "STEP") (pinfunction "STEP_STEP") (pintype "input"))
      (node (ref "U1") (pin "4") (pinfunction "PE5_4") (pintype "bidirectional"))
    )
    (net (code "37") (name "MOT_Y0_DIR") (class "Default")
      (node (ref "U$3") (pin "DIR") (pinfunction "DIR_DIR") (pintype "input"))
      (node (ref "U1") (pin "98") (pinfunction "PE1_98") (pintype "bidirectional"))
    )
    (net (code "38") (name "MOT_Y0_EN") (class "Default")
      (node (ref "U$3") (pin "EN") (pinfunction "EN_EN") (pintype "input"))
      (node (ref "U1") (pin "2") (pinfunction "PE3_2") (pintype "bidirectional"))
    )
    (net (code "39") (name "MOT_Y0_STEP") (class "Default")
      (node (ref "U$3") (pin "STEP") (pinfunction "STEP_STEP") (pintype "input"))
      (node (ref "U1") (pin "1") (pinfunction "PE2_1") (pintype "bidirectional"))
    )
    (net (code "40") (name "MOT_Y1_DIR") (class "Default")
      (node (ref "U$4") (pin "DIR") (pinfunction "DIR_DIR") (pintype "input"))
      (node (ref "U1") (pin "95") (pinfunction "PB8_95") (pintype "bidirectional"))
    )
    (net (code "41") (name "MOT_Y1_EN") (class "Default")
      (node (ref "U$4") (pin "EN") (pinfunction "EN_EN") (pintype "input"))
      (node (ref "U1") (pin "97") (pinfunction "PE0_97") (pintype "bidirectional"))
    )
    (net (code "42") (name "MOT_Y1_STEP") (class "Default")
      (node (ref "U$4") (pin "STEP") (pinfunction "STEP_STEP") (pintype "input"))
      (node (ref "U1") (pin "96") (pinfunction "PB9_96") (pintype "bidirectional"))
    )
    (net (code "43") (name "MOT_Z_DIR") (class "Default")
      (node (ref "U$5") (pin "DIR") (pinfunction "DIR_DIR") (pintype "input"))
      (node (ref "U1") (pin "88") (pinfunction "PD7_88") (pintype "bidirectional"))
    )
    (net (code "44") (name "MOT_Z_EN") (class "Default")
      (node (ref "U$5") (pin "EN") (pinfunction "EN_EN") (pintype "input"))
      (node (ref "U1") (pin "91") (pinfunction "PB5_91") (pintype "bidirectional"))
    )
    (net (code "45") (name "MOT_Z_STEP") (class "Default")
      (node (ref "U$5") (pin "STEP") (pinfunction "STEP_STEP") (pintype "input"))
      (node (ref "U1") (pin "90") (pinfunction "PB4_90") (pintype "bidirectional"))
    )
    (net (code "46") (name "NRST") (class "Default")
      (node (ref "C29") (pin "1") (pinfunction "1_1") (pintype "bidirectional"))
      (node (ref "R29") (pin "2") (pinfunction "2_2") (pintype "passive"))
      (node (ref "S1") (pin "1A") (pinfunction "1_1A") (pintype "bidirectional"))
      (node (ref "S1") (pin "1B") (pinfunction "2_1B") (pintype "bidirectional"))
      (node (ref "U1") (pin "14") (pinfunction "NRST_14") (pintype "bidirectional"))
      (node (ref "X21") (pin "P$3") (pinfunction "1_P$3") (pintype "passive"))
    )
    (net (code "47") (name "Net-(C1-1)") (class "Default")
      (node (ref "C1") (pin "P$1") (pinfunction "1_P$1") (pintype "bidirectional"))
      (node (ref "C43") (pin "1") (pinfunction "1_1") (pintype "bidirectional"))
      (node (ref "U1") (pin "48") (pinfunction "VCAP_1_48") (pintype "power_in"))
      (node (ref "U1") (pin "73") (pinfunction "VCAP_2_73") (pintype "power_in"))
    )
    (net (code "48") (name "Net-(C36-2)") (class "Default")
      (node (ref "C36") (pin "P$2") (pinfunction "2_P$2") (pintype "bidirectional"))
      (node (ref "U4") (pin "14") (pinfunction "VDD18_14") (pintype "bidirectional"))
    )
    (net (code "49") (name "Net-(C39-2)") (class "Default")
      (node (ref "C39") (pin "P$2") (pinfunction "2_P$2") (pintype "bidirectional"))
      (node (ref "U4") (pin "13") (pinfunction "VDD3_13") (pintype "bidirectional"))
    )
    (net (code "50") (name "Net-(D1-Pad2)") (class "Default")
      (node (ref "D1") (pin "2") (pinfunction "2_2") (pintype "bidirectional"))
      (node (ref "R18") (pin "2") (pinfunction "2_2") (pintype "passive"))
    )
    (net (code "51") (name "Net-(D2-ANODE)") (class "Default")
      (node (ref "D2") (pin "A") (pinfunction "ANODE_A") (pintype "bidirectional"))
      (node (ref "R20") (pin "1") (pinfunction "1_1") (pintype "passive"))
      (node (ref "U$22") (pin "D") (pinfunction "D_D") (pintype "bidirectional"))
      (node (ref "X14") (pin "P$1") (pinfunction "1_P$1") (pintype "passive"))
    )
    (net (code "52") (name "Net-(D3-Pad2)") (class "Default")
      (node (ref "D3") (pin "2") (pinfunction "2_2") (pintype "bidirectional"))
      (node (ref "R20") (pin "2") (pinfunction "2_2") (pintype "passive"))
    )
    (net (code "53") (name "Net-(D5-ANODE)") (class "Default")
      (node (ref "D5") (pin "A") (pinfunction "ANODE_A") (pintype "bidirectional"))
      (node (ref "R22") (pin "1") (pinfunction "1_1") (pintype "passive"))
      (node (ref "U$23") (pin "D") (pinfunction "D_D") (pintype "bidirectional"))
      (node (ref "X15") (pin "P$1") (pinfunction "1_P$1") (pintype "passive"))
    )
    (net (code "54") (name "Net-(D6-Pad2)") (class "Default")
      (node (ref "D6") (pin "2") (pinfunction "2_2") (pintype "bidirectional"))
      (node (ref "R22") (pin "2") (pinfunction "2_2") (pintype "passive"))
    )
    (net (code "55") (name "Net-(D7-ANODE)") (class "Default")
      (node (ref "D7") (pin "A") (pinfunction "ANODE_A") (pintype "bidirectional"))
      (node (ref "R24") (pin "1") (pinfunction "1_1") (pintype "passive"))
      (node (ref "U$24") (pin "D") (pinfunction "D_D") (pintype "bidirectional"))
      (node (ref "X16") (pin "P$1") (pinfunction "1_P$1") (pintype "passive"))
    )
    (net (code "56") (name "Net-(D8-Pad2)") (class "Default")
      (node (ref "D8") (pin "2") (pinfunction "2_2") (pintype "bidirectional"))
      (node (ref "R24") (pin "2") (pinfunction "2_2") (pintype "passive"))
    )
    (net (code "57") (name "Net-(D9-ANODE)") (class "Default")
      (node (ref "D9") (pin "A") (pinfunction "ANODE_A") (pintype "bidirectional"))
      (node (ref "R26") (pin "1") (pinfunction "1_1") (pintype "passive"))
      (node (ref "U$25") (pin "D") (pinfunction "D_D") (pintype "bidirectional"))
      (node (ref "X17") (pin "P$1") (pinfunction "1_P$1") (pintype "passive"))
    )
    (net (code "58") (name "Net-(D10-Pad1)") (class "Default")
      (node (ref "D10") (pin "1") (pinfunction "1_1") (pintype "bidirectional"))
      (node (ref "F1") (pin "2") (pinfunction "2_2") (pintype "passive"))
    )
    (net (code "59") (name "Net-(D11-Pad2)") (class "Default")
      (node (ref "D11") (pin "2") (pinfunction "2_2") (pintype "bidirectional"))
      (node (ref "R26") (pin "2") (pinfunction "2_2") (pintype "passive"))
    )
    (net (code "60") (name "Net-(D13-ANODE)") (class "Default")
      (node (ref "D13") (pin "A") (pinfunction "ANODE_A") (pintype "bidirectional"))
      (node (ref "R18") (pin "1") (pinfunction "1_1") (pintype "passive"))
      (node (ref "U$21") (pin "D") (pinfunction "D_D") (pintype "bidirectional"))
      (node (ref "X13") (pin "P$1") (pinfunction "1_P$1") (pintype "passive"))
    )
    (net (code "61") (name "Net-(D14-ANODE)") (class "Default")
      (node (ref "D14") (pin "A") (pinfunction "ANODE_A") (pintype "bidirectional"))
      (node (ref "R28") (pin "1") (pinfunction "1_1") (pintype "passive"))
      (node (ref "U$26") (pin "D") (pinfunction "D_D") (pintype "bidirectional"))
      (node (ref "X18") (pin "P$1") (pinfunction "1_P$1") (pintype "passive"))
    )
    (net (code "62") (name "Net-(D15-Pad2)") (class "Default")
      (node (ref "D15") (pin "2") (pinfunction "2_2") (pintype "bidirectional"))
      (node (ref "R28") (pin "2") (pinfunction "2_2") (pintype "passive"))
    )
    (net (code "63") (name "Net-(J1-+5V)") (class "Default")
      (node (ref "F1") (pin "1") (pinfunction "1_1") (pintype "passive"))
      (node (ref "J1") (pin "1") (pinfunction "+5V_1") (pintype "bidirectional"))
    )
    (net (code "64") (name "Net-(L1-1)") (class "Default")
      (node (ref "C50") (pin "1") (pinfunction "1_1") (pintype "bidirectional"))
      (node (ref "L1") (pin "P$1") (pinfunction "1_P$1") (pintype "passive"))
      (node (ref "U3") (pin "6") (pinfunction "SW_6") (pintype "output"))
    )
    (net (code "65") (name "Net-(L2-1)") (class "Default")
      (node (ref "C57") (pin "1") (pinfunction "1_1") (pintype "bidirectional"))
      (node (ref "L2") (pin "P$1") (pinfunction "1_P$1") (pintype "passive"))
      (node (ref "U5") (pin "6") (pinfunction "SW_6") (pintype "output"))
    )
    (net (code "66") (name "Net-(R17-Pad2)") (class "Default")
      (node (ref "R17") (pin "2") (pinfunction "2_2") (pintype "passive"))
      (node (ref "R40") (pin "1") (pinfunction "1_1") (pintype "passive"))
      (node (ref "U$21") (pin "G") (pinfunction "G_G") (pintype "bidirectional"))
    )
    (net (code "67") (name "Net-(R19-Pad2)") (class "Default")
      (node (ref "R19") (pin "2") (pinfunction "2_2") (pintype "passive"))
      (node (ref "R41") (pin "1") (pinfunction "1_1") (pintype "passive"))
      (node (ref "U$22") (pin "G") (pinfunction "G_G") (pintype "bidirectional"))
    )
    (net (code "68") (name "Net-(R21-Pad2)") (class "Default")
      (node (ref "R21") (pin "2") (pinfunction "2_2") (pintype "passive"))
      (node (ref "R42") (pin "1") (pinfunction "1_1") (pintype "passive"))
      (node (ref "U$23") (pin "G") (pinfunction "G_G") (pintype "bidirectional"))
    )
    (net (code "69") (name "Net-(R23-Pad2)") (class "Default")
      (node (ref "R23") (pin "2") (pinfunction "2_2") (pintype "passive"))
      (node (ref "R43") (pin "1") (pinfunction "1_1") (pintype "passive"))
      (node (ref "U$24") (pin "G") (pinfunction "G_G") (pintype "bidirectional"))
    )
    (net (code "70") (name "Net-(R25-Pad2)") (class "Default")
      (node (ref "R25") (pin "2") (pinfunction "2_2") (pintype "passive"))
      (node (ref "R44") (pin "1") (pinfunction "1_1") (pintype "passive"))
      (node (ref "U$25") (pin "G") (pinfunction "G_G") (pintype "bidirectional"))
    )
    (net (code "71") (name "Net-(R27-Pad2)") (class "Default")
      (node (ref "R27") (pin "2") (pinfunction "2_2") (pintype "passive"))
      (node (ref "R45") (pin "1") (pinfunction "1_1") (pintype "passive"))
      (node (ref "U$26") (pin "G") (pinfunction "G_G") (pintype "bidirectional"))
    )
    (net (code "72") (name "Net-(R38-Pad1)") (class "Default")
      (node (ref "R38") (pin "1") (pinfunction "1_1") (pintype "passive"))
      (node (ref "R39") (pin "1") (pinfunction "1_1") (pintype "passive"))
    )
    (net (code "73") (name "Net-(U$2-SLEEP)") (class "Default")
      (node (ref "U$2") (pin "RST") (pinfunction "RST_RST") (pintype "input"))
      (node (ref "U$2") (pin "SLP") (pinfunction "SLEEP_SLP") (pintype "input"))
    )
    (net (code "74") (name "Net-(U$3-SLEEP)") (class "Default")
      (node (ref "U$3") (pin "RST") (pinfunction "RST_RST") (pintype "input"))
      (node (ref "U$3") (pin "SLP") (pinfunction "SLEEP_SLP") (pintype "input"))
    )
    (net (code "75") (name "Net-(U$4-SLEEP)") (class "Default")
      (node (ref "U$4") (pin "RST") (pinfunction "RST_RST") (pintype "input"))
      (node (ref "U$4") (pin "SLP") (pinfunction "SLEEP_SLP") (pintype "input"))
    )
    (net (code "76") (name "Net-(U$5-SLEEP)") (class "Default")
      (node (ref "U$5") (pin "RST") (pinfunction "RST_RST") (pintype "input"))
      (node (ref "U$5") (pin "SLP") (pinfunction "SLEEP_SLP") (pintype "input"))
    )
    (net (code "77") (name "Net-(U$6-SLEEP)") (class "Default")
      (node (ref "U$6") (pin "RST") (pinfunction "RST_RST") (pintype "input"))
      (node (ref "U$6") (pin "SLP") (pinfunction "SLEEP_SLP") (pintype "input"))
    )
    (net (code "78") (name "Net-(U$7-SLEEP)") (class "Default")
      (node (ref "U$7") (pin "RST") (pinfunction "RST_RST") (pintype "input"))
      (node (ref "U$7") (pin "SLP") (pinfunction "SLEEP_SLP") (pintype "input"))
    )
    (net (code "79") (name "Net-(U$8-SLEEP)") (class "Default")
      (node (ref "U$8") (pin "RST") (pinfunction "RST_RST") (pintype "input"))
      (node (ref "U$8") (pin "SLP") (pinfunction "SLEEP_SLP") (pintype "input"))
    )
    (net (code "80") (name "Net-(U$9-SLEEP)") (class "Default")
      (node (ref "U$9") (pin "RST") (pinfunction "RST_RST") (pintype "input"))
      (node (ref "U$9") (pin "SLP") (pinfunction "SLEEP_SLP") (pintype "input"))
    )
    (net (code "81") (name "Net-(U1B-BOOT0)") (class "Default")
      (node (ref "R30") (pin "1") (pinfunction "1_1") (pintype "passive"))
      (node (ref "U1") (pin "94") (pinfunction "BOOT0_94") (pintype "input"))
    )
    (net (code "82") (name "Net-(U1B-PH0-OSC_IN)") (class "Default")
      (node (ref "C30") (pin "1") (pinfunction "1_1") (pintype "bidirectional"))
      (node (ref "U1") (pin "12") (pinfunction "PH0-OSC_IN_12") (pintype "bidirectional"))
      (node (ref "Y1") (pin "3") (pinfunction "3_3") (pintype "bidirectional"))
    )
    (net (code "83") (name "Net-(U1B-PH1)") (class "Default")
      (node (ref "C31") (pin "1") (pinfunction "1_1") (pintype "bidirectional"))
      (node (ref "U1") (pin "13") (pinfunction "PH1_13") (pintype "bidirectional"))
      (node (ref "Y1") (pin "1") (pinfunction "1_1") (pintype "bidirectional"))
    )
    (net (code "84") (name "Net-(U2-DTR#)") (class "Default")
      (node (ref "R3") (pin "1") (pinfunction "1_1") (pintype "passive"))
      (node (ref "U2") (pin "13") (pinfunction "DTR#_13") (pintype "bidirectional"))
    )
    (net (code "85") (name "Net-(U2-RXD)") (class "Default")
      (node (ref "R2") (pin "1") (pinfunction "1_1") (pintype "passive"))
      (node (ref "U2") (pin "3") (pinfunction "RXD_3") (pintype "bidirectional"))
    )
    (net (code "86") (name "Net-(U2-TXD)") (class "Default")
      (node (ref "R1") (pin "1") (pinfunction "1_1") (pintype "passive"))
      (node (ref "U2") (pin "2") (pinfunction "TXD_2") (pintype "bidirectional"))
    )
    (net (code "87") (name "Net-(U2-V3)") (class "Default")
      (node (ref "C16") (pin "2") (pinfunction "2_2") (pintype "bidirectional"))
      (node (ref "U2") (pin "4") (pinfunction "V3_4") (pintype "bidirectional"))
    )
    (net (code "88") (name "Net-(U2-XI)") (class "Default")
      (node (ref "C18") (pin "2") (pinfunction "2_2") (pintype "bidirectional"))
      (node (ref "U2") (pin "7") (pinfunction "XI_7") (pintype "bidirectional"))
      (node (ref "Y2") (pin "1") (pinfunction "1_1") (pintype "bidirectional"))
    )
    (net (code "89") (name "Net-(U2-XO)") (class "Default")
      (node (ref "C19") (pin "2") (pinfunction "2_2") (pintype "bidirectional"))
      (node (ref "U2") (pin "8") (pinfunction "XO_8") (pintype "bidirectional"))
      (node (ref "Y2") (pin "3") (pinfunction "3_3") (pintype "bidirectional"))
    )
    (net (code "90") (name "Net-(U3-EN)") (class "Default")
      (node (ref "R33") (pin "2") (pinfunction "2_2") (pintype "passive"))
      (node (ref "U3") (pin "1") (pinfunction "EN_1") (pintype "input"))
    )
    (net (code "91") (name "Net-(U3-SS)") (class "Default")
      (node (ref "C52") (pin "1") (pinfunction "1_1") (pintype "bidirectional"))
      (node (ref "U3") (pin "4") (pinfunction "SS_4") (pintype "output"))
    )
    (net (code "92") (name "Net-(U3-VBST)") (class "Default")
      (node (ref "C50") (pin "2") (pinfunction "2_2") (pintype "bidirectional"))
      (node (ref "U3") (pin "7") (pinfunction "VBST_7") (pintype "input"))
    )
    (net (code "93") (name "Net-(U3-VFB)") (class "Default")
      (node (ref "C51") (pin "2") (pinfunction "2_2") (pintype "bidirectional"))
      (node (ref "R34") (pin "1") (pinfunction "1_1") (pintype "passive"))
      (node (ref "R35") (pin "2") (pinfunction "2_2") (pintype "passive"))
      (node (ref "U3") (pin "2") (pinfunction "VFB_2") (pintype "input"))
    )
    (net (code "94") (name "Net-(U3-VREG5)") (class "Default")
      (node (ref "C53") (pin "1") (pinfunction "1_1") (pintype "bidirectional"))
      (node (ref "U3") (pin "3") (pinfunction "VREG5_3") (pintype "bidirectional"))
    )
    (net (code "95") (name "Net-(U4-XIN)") (class "Default")
      (node (ref "C41") (pin "1") (pinfunction "1_1") (pintype "bidirectional"))
      (node (ref "U4") (pin "16") (pinfunction "XIN_16") (pintype "bidirectional"))
      (node (ref "Y3") (pin "3") (pinfunction "3_3") (pintype "bidirectional"))
    )
    (net (code "96") (name "Net-(U4-XOUT)") (class "Default")
      (node (ref "C4") (pin "1") (pinfunction "1_1") (pintype "bidirectional"))
      (node (ref "U4") (pin "15") (pinfunction "XOUT_15") (pintype "bidirectional"))
      (node (ref "Y3") (pin "1") (pinfunction "1_1") (pintype "bidirectional"))
    )
    (net (code "97") (name "Net-(U5-EN)") (class "Default")
      (node (ref "R36") (pin "2") (pinfunction "2_2") (pintype "passive"))
      (node (ref "U5") (pin "1") (pinfunction "EN_1") (pintype "input"))
    )
    (net (code "98") (name "Net-(U5-SS)") (class "Default")
      (node (ref "C59") (pin "1") (pinfunction "1_1") (pintype "bidirectional"))
      (node (ref "U5") (pin "4") (pinfunction "SS_4") (pintype "output"))
    )
    (net (code "99") (name "Net-(U5-VBST)") (class "Default")
      (node (ref "C57") (pin "2") (pinfunction "2_2") (pintype "bidirectional"))
      (node (ref "U5") (pin "7") (pinfunction "VBST_7") (pintype "input"))
    )
    (net (code "100") (name "Net-(U5-VFB)") (class "Default")
      (node (ref "C58") (pin "2") (pinfunction "2_2") (pintype "bidirectional"))
      (node (ref "R37") (pin "1") (pinfunction "1_1") (pintype "passive"))
      (node (ref "R38") (pin "2") (pinfunction "2_2") (pintype "passive"))
      (node (ref "U5") (pin "2") (pinfunction "VFB_2") (pintype "input"))
    )
    (net (code "101") (name "Net-(U5-VREG5)") (class "Default")
      (node (ref "C60") (pin "1") (pinfunction "1_1") (pintype "bidirectional"))
      (node (ref "U5") (pin "3") (pinfunction "VREG5_3") (pintype "bidirectional"))
    )
    (net (code "102") (name "Net-(X1A-1)") (class "Default")
      (node (ref "U$2") (pin "2B") (pinfunction "2B_2B") (pintype "output"))
      (node (ref "X1") (pin "P$1") (pinfunction "1_P$1") (pintype "passive"))
    )
    (net (code "103") (name "Net-(X1B-1)") (class "Default")
      (node (ref "U$2") (pin "2A") (pinfunction "2A_2A") (pintype "output"))
      (node (ref "X1") (pin "P$2") (pinfunction "1_P$2") (pintype "passive"))
    )
    (net (code "104") (name "Net-(X1C-1)") (class "Default")
      (node (ref "U$2") (pin "1A") (pinfunction "1A_1A") (pintype "output"))
      (node (ref "X1") (pin "P$3") (pinfunction "1_P$3") (pintype "passive"))
    )
    (net (code "105") (name "Net-(X1D-1)") (class "Default")
      (node (ref "U$2") (pin "1B") (pinfunction "1B_1B") (pintype "output"))
      (node (ref "X1") (pin "P$4") (pinfunction "1_P$4") (pintype "passive"))
    )
    (net (code "106") (name "Net-(X2A-1)") (class "Default")
      (node (ref "U$3") (pin "2B") (pinfunction "2B_2B") (pintype "output"))
      (node (ref "X2") (pin "P$1") (pinfunction "1_P$1") (pintype "passive"))
    )
    (net (code "107") (name "Net-(X2B-1)") (class "Default")
      (node (ref "U$3") (pin "2A") (pinfunction "2A_2A") (pintype "output"))
      (node (ref "X2") (pin "P$2") (pinfunction "1_P$2") (pintype "passive"))
    )
    (net (code "108") (name "Net-(X2C-1)") (class "Default")
      (node (ref "U$3") (pin "1A") (pinfunction "1A_1A") (pintype "output"))
      (node (ref "X2") (pin "P$3") (pinfunction "1_P$3") (pintype "passive"))
    )
    (net (code "109") (name "Net-(X2D-1)") (class "Default")
      (node (ref "U$3") (pin "1B") (pinfunction "1B_1B") (pintype "output"))
      (node (ref "X2") (pin "P$4") (pinfunction "1_P$4") (pintype "passive"))
    )
    (net (code "110") (name "Net-(X3A-1)") (class "Default")
      (node (ref "U$4") (pin "2B") (pinfunction "2B_2B") (pintype "output"))
      (node (ref "X3") (pin "P$1") (pinfunction "1_P$1") (pintype "passive"))
    )
    (net (code "111") (name "Net-(X3B-1)") (class "Default")
      (node (ref "U$4") (pin "2A") (pinfunction "2A_2A") (pintype "output"))
      (node (ref "X3") (pin "P$2") (pinfunction "1_P$2") (pintype "passive"))
    )
    (net (code "112") (name "Net-(X3C-1)") (class "Default")
      (node (ref "U$4") (pin "1A") (pinfunction "1A_1A") (pintype "output"))
      (node (ref "X3") (pin "P$3") (pinfunction "1_P$3") (pintype "passive"))
    )
    (net (code "113") (name "Net-(X3D-1)") (class "Default")
      (node (ref "U$4") (pin "1B") (pinfunction "1B_1B") (pintype "output"))
      (node (ref "X3") (pin "P$4") (pinfunction "1_P$4") (pintype "passive"))
    )
    (net (code "114") (name "Net-(X4A-1)") (class "Default")
      (node (ref "U$5") (pin "2B") (pinfunction "2B_2B") (pintype "output"))
      (node (ref "X4") (pin "P$1") (pinfunction "1_P$1") (pintype "passive"))
    )
    (net (code "115") (name "Net-(X4B-1)") (class "Default")
      (node (ref "U$5") (pin "2A") (pinfunction "2A_2A") (pintype "output"))
      (node (ref "X4") (pin "P$2") (pinfunction "1_P$2") (pintype "passive"))
    )
    (net (code "116") (name "Net-(X4C-1)") (class "Default")
      (node (ref "U$5") (pin "1A") (pinfunction "1A_1A") (pintype "output"))
      (node (ref "X4") (pin "P$3") (pinfunction "1_P$3") (pintype "passive"))
    )
    (net (code "117") (name "Net-(X4D-1)") (class "Default")
      (node (ref "U$5") (pin "1B") (pinfunction "1B_1B") (pintype "output"))
      (node (ref "X4") (pin "P$4") (pinfunction "1_P$4") (pintype "passive"))
    )
    (net (code "118") (name "Net-(X5A-1)") (class "Default")
      (node (ref "U$6") (pin "2B") (pinfunction "2B_2B") (pintype "output"))
      (node (ref "X5") (pin "P$1") (pinfunction "1_P$1") (pintype "passive"))
    )
    (net (code "119") (name "Net-(X5B-1)") (class "Default")
      (node (ref "U$6") (pin "2A") (pinfunction "2A_2A") (pintype "output"))
      (node (ref "X5") (pin "P$2") (pinfunction "1_P$2") (pintype "passive"))
    )
    (net (code "120") (name "Net-(X5C-1)") (class "Default")
      (node (ref "U$6") (pin "1A") (pinfunction "1A_1A") (pintype "output"))
      (node (ref "X5") (pin "P$3") (pinfunction "1_P$3") (pintype "passive"))
    )
    (net (code "121") (name "Net-(X5D-1)") (class "Default")
      (node (ref "U$6") (pin "1B") (pinfunction "1B_1B") (pintype "output"))
      (node (ref "X5") (pin "P$4") (pinfunction "1_P$4") (pintype "passive"))
    )
    (net (code "122") (name "Net-(X6A-1)") (class "Default")
      (node (ref "U$7") (pin "2B") (pinfunction "2B_2B") (pintype "output"))
      (node (ref "X6") (pin "P$1") (pinfunction "1_P$1") (pintype "passive"))
    )
    (net (code "123") (name "Net-(X6B-1)") (class "Default")
      (node (ref "U$7") (pin "2A") (pinfunction "2A_2A") (pintype "output"))
      (node (ref "X6") (pin "P$2") (pinfunction "1_P$2") (pintype "passive"))
    )
    (net (code "124") (name "Net-(X6C-1)") (class "Default")
      (node (ref "U$7") (pin "1A") (pinfunction "1A_1A") (pintype "output"))
      (node (ref "X6") (pin "P$3") (pinfunction "1_P$3") (pintype "passive"))
    )
    (net (code "125") (name "Net-(X6D-1)") (class "Default")
      (node (ref "U$7") (pin "1B") (pinfunction "1B_1B") (pintype "output"))
      (node (ref "X6") (pin "P$4") (pinfunction "1_P$4") (pintype "passive"))
    )
    (net (code "126") (name "Net-(X7A-1)") (class "Default")
      (node (ref "R4") (pin "2") (pinfunction "2_2") (pintype "passive"))
      (node (ref "R5") (pin "1") (pinfunction "1_1") (pintype "passive"))
      (node (ref "X7") (pin "P$1") (pinfunction "1_P$1") (pintype "passive"))
    )
    (net (code "127") (name "Net-(X8A-1)") (class "Default")
      (node (ref "R6") (pin "1") (pinfunction "1_1") (pintype "passive"))
      (node (ref "R7") (pin "2") (pinfunction "2_2") (pintype "passive"))
      (node (ref "X8") (pin "P$1") (pinfunction "1_P$1") (pintype "passive"))
    )
    (net (code "128") (name "Net-(X9A-1)") (class "Default")
      (node (ref "R8") (pin "1") (pinfunction "1_1") (pintype "passive"))
      (node (ref "R9") (pin "2") (pinfunction "2_2") (pintype "passive"))
      (node (ref "X9") (pin "P$1") (pinfunction "1_P$1") (pintype "passive"))
    )
    (net (code "129") (name "Net-(X10A-1)") (class "Default")
      (node (ref "R10") (pin "1") (pinfunction "1_1") (pintype "passive"))
      (node (ref "R11") (pin "2") (pinfunction "2_2") (pintype "passive"))
      (node (ref "X10") (pin "P$1") (pinfunction "1_P$1") (pintype "passive"))
    )
    (net (code "130") (name "Net-(X11A-1)") (class "Default")
      (node (ref "R12") (pin "1") (pinfunction "1_1") (pintype "passive"))
      (node (ref "R13") (pin "2") (pinfunction "2_2") (pintype "passive"))
      (node (ref "X11") (pin "P$1") (pinfunction "1_P$1") (pintype "passive"))
    )
    (net (code "131") (name "Net-(X12A-1)") (class "Default")
      (node (ref "R14") (pin "1") (pinfunction "1_1") (pintype "passive"))
      (node (ref "R15") (pin "2") (pinfunction "2_2") (pintype "passive"))
      (node (ref "X12") (pin "P$1") (pinfunction "1_P$1") (pintype "passive"))
    )
    (net (code "132") (name "Net-(X25A-1)") (class "Default")
      (node (ref "U$8") (pin "2B") (pinfunction "2B_2B") (pintype "output"))
      (node (ref "X25") (pin "P$1") (pinfunction "1_P$1") (pintype "passive"))
    )
    (net (code "133") (name "Net-(X25B-1)") (class "Default")
      (node (ref "U$8") (pin "2A") (pinfunction "2A_2A") (pintype "output"))
      (node (ref "X25") (pin "P$2") (pinfunction "1_P$2") (pintype "passive"))
    )
    (net (code "134") (name "Net-(X25C-1)") (class "Default")
      (node (ref "U$8") (pin "1A") (pinfunction "1A_1A") (pintype "output"))
      (node (ref "X25") (pin "P$3") (pinfunction "1_P$3") (pintype "passive"))
    )
    (net (code "135") (name "Net-(X25D-1)") (class "Default")
      (node (ref "U$8") (pin "1B") (pinfunction "1B_1B") (pintype "output"))
      (node (ref "X25") (pin "P$4") (pinfunction "1_P$4") (pintype "passive"))
    )
    (net (code "136") (name "Net-(X33A-1)") (class "Default")
      (node (ref "U$9") (pin "2B") (pinfunction "2B_2B") (pintype "output"))
      (node (ref "X33") (pin "P$1") (pinfunction "1_P$1") (pintype "passive"))
    )
    (net (code "137") (name "Net-(X33B-1)") (class "Default")
      (node (ref "U$9") (pin "2A") (pinfunction "2A_2A") (pintype "output"))
      (node (ref "X33") (pin "P$2") (pinfunction "1_P$2") (pintype "passive"))
    )
    (net (code "138") (name "Net-(X33C-1)") (class "Default")
      (node (ref "U$9") (pin "1A") (pinfunction "1A_1A") (pintype "output"))
      (node (ref "X33") (pin "P$3") (pinfunction "1_P$3") (pintype "passive"))
    )
    (net (code "139") (name "Net-(X33D-1)") (class "Default")
      (node (ref "U$9") (pin "1B") (pinfunction "1B_1B") (pintype "output"))
      (node (ref "X33") (pin "P$4") (pinfunction "1_P$4") (pintype "passive"))
    )
    (net (code "140") (name "OUTPUT_LED_BOT_UP") (class "Default")
      (node (ref "R42") (pin "2") (pinfunction "2_2") (pintype "passive"))
      (node (ref "U1") (pin "61") (pinfunction "PD14_61") (pintype "bidirectional"))
    )
    (net (code "141") (name "OUTPUT_LED_TOP_DN") (class "Default")
      (node (ref "R43") (pin "2") (pinfunction "2_2") (pintype "passive"))
      (node (ref "U1") (pin "60") (pinfunction "PD13_60") (pintype "bidirectional"))
    )
    (net (code "142") (name "OUTPUT_LED_TRAY_1") (class "Default")
      (node (ref "R44") (pin "2") (pinfunction "2_2") (pintype "passive"))
      (node (ref "U1") (pin "59") (pinfunction "PD12_59") (pintype "bidirectional"))
    )
    (net (code "143") (name "OUTPUT_LED_TRAY_2") (class "Default")
      (node (ref "R45") (pin "2") (pinfunction "2_2") (pintype "passive"))
      (node (ref "U1") (pin "58") (pinfunction "PD11_58") (pintype "bidirectional"))
    )
    (net (code "144") (name "OUTPUT_PUMP") (class "Default")
      (node (ref "R40") (pin "2") (pinfunction "2_2") (pintype "passive"))
      (node (ref "U1") (pin "63") (pinfunction "PC6_63") (pintype "bidirectional"))
    )
    (net (code "145") (name "OUTPUT_VALVE") (class "Default")
      (node (ref "R41") (pin "2") (pinfunction "2_2") (pintype "passive"))
      (node (ref "U1") (pin "62") (pinfunction "PD15_62") (pintype "bidirectional"))
    )
    (net (code "146") (name "PA0{slash}ADC0") (class "Default")
      (node (ref "U1") (pin "23") (pinfunction "PA0_23") (pintype "bidirectional"))
      (node (ref "X27") (pin "P$1") (pinfunction "1_P$1") (pintype "passive"))
    )
    (net (code "147") (name "PA1{slash}ADC1") (class "Default")
      (node (ref "U1") (pin "24") (pinfunction "PA1_24") (pintype "bidirectional"))
      (node (ref "X27") (pin "P$2") (pinfunction "1_P$2") (pintype "passive"))
    )
    (net (code "148") (name "PA2{slash}ADC2") (class "Default")
      (node (ref "U1") (pin "25") (pinfunction "PA2_25") (pintype "bidirectional"))
      (node (ref "X27") (pin "P$3") (pinfunction "1_P$3") (pintype "passive"))
    )
    (net (code "149") (name "PA3{slash}ADC3") (class "Default")
      (node (ref "U1") (pin "26") (pinfunction "PA3_26") (pintype "bidirectional"))
      (node (ref "X27") (pin "P$4") (pinfunction "1_P$4") (pintype "passive"))
    )
    (net (code "150") (name "PA4") (class "Default")
      (node (ref "U1") (pin "29") (pinfunction "PA4_29") (pintype "bidirectional"))
      (node (ref "X28") (pin "P$1") (pinfunction "1_P$1") (pintype "passive"))
    )
    (net (code "151") (name "PA5{slash}SPI1_SCK") (class "Default")
      (node (ref "U1") (pin "30") (pinfunction "PA5_30") (pintype "bidirectional"))
      (node (ref "X26") (pin "P$2") (pinfunction "1_P$2") (pintype "passive"))
    )
    (net (code "152") (name "PA6{slash}SPI1_MISO") (class "Default")
      (node (ref "U1") (pin "31") (pinfunction "PA6_31") (pintype "bidirectional"))
      (node (ref "X26") (pin "P$3") (pinfunction "1_P$3") (pintype "passive"))
    )
    (net (code "153") (name "PA7{slash}SPI1_MOSI") (class "Default")
      (node (ref "U1") (pin "32") (pinfunction "PA7_32") (pintype "bidirectional"))
      (node (ref "X26") (pin "P$4") (pinfunction "1_P$4") (pintype "passive"))
    )
    (net (code "154") (name "PB0") (class "Default")
      (node (ref "U1") (pin "35") (pinfunction "PB0_35") (pintype "bidirectional"))
      (node (ref "X28") (pin "P$4") (pinfunction "1_P$4") (pintype "passive"))
    )
    (net (code "155") (name "PB6{slash}I2C1_SCL") (class "Default")
      (node (ref "R16") (pin "2") (pinfunction "2_2") (pintype "passive"))
      (node (ref "U1") (pin "92") (pinfunction "PB6_92") (pintype "bidirectional"))
      (node (ref "X19") (pin "P$1") (pinfunction "1_P$1") (pintype "passive"))
      (node (ref "X20") (pin "P$1") (pinfunction "1_P$1") (pintype "passive"))
    )
    (net (code "156") (name "PB7{slash}I2C1_SDA") (class "Default")
      (node (ref "R31") (pin "2") (pinfunction "2_2") (pintype "passive"))
      (node (ref "U1") (pin "93") (pinfunction "PB7_93") (pintype "bidirectional"))
      (node (ref "X19") (pin "P$2") (pinfunction "1_P$2") (pintype "passive"))
      (node (ref "X20") (pin "P$2") (pinfunction "1_P$2") (pintype "passive"))
    )
    (net (code "157") (name "PB12{slash}BUSY") (class "Default")
      (node (ref "R32") (pin "2") (pinfunction "2_2") (pintype "passive"))
      (node (ref "U1") (pin "51") (pinfunction "PB12_51") (pintype "bidirectional"))
      (node (ref "X19") (pin "P$3") (pinfunction "1_P$3") (pintype "passive"))
      (node (ref "X20") (pin "P$3") (pinfunction "1_P$3") (pintype "passive"))
    )
    (net (code "158") (name "PC4") (class "Default")
      (node (ref "U1") (pin "33") (pinfunction "PC4_33") (pintype "bidirectional"))
      (node (ref "X28") (pin "P$2") (pinfunction "1_P$2") (pintype "passive"))
    )
    (net (code "159") (name "PC5") (class "Default")
      (node (ref "U1") (pin "34") (pinfunction "PC5_34") (pintype "bidirectional"))
      (node (ref "X28") (pin "P$3") (pinfunction "1_P$3") (pintype "passive"))
    )
    (net (code "160") (name "RX") (class "Default")
      (node (ref "R1") (pin "2") (pinfunction "2_2") (pintype "passive"))
      (node (ref "U1") (pin "69") (pinfunction "PA10_69") (pintype "bidirectional"))
    )
    (net (code "161") (name "SYS_JTC") (class "Default")
      (node (ref "U1") (pin "76") (pinfunction "PA14_76") (pintype "bidirectional"))
      (node (ref "X21") (pin "P$2") (pinfunction "1_P$2") (pintype "passive"))
    )
    (net (code "162") (name "SYS_JTMS-SWDIO") (class "Default")
      (node (ref "U1") (pin "72") (pinfunction "PA13_72") (pintype "bidirectional"))
      (node (ref "X21") (pin "P$1") (pinfunction "1_P$1") (pintype "passive"))
    )
    (net (code "163") (name "TX") (class "Default")
      (node (ref "R2") (pin "2") (pinfunction "2_2") (pintype "passive"))
      (node (ref "U1") (pin "68") (pinfunction "PA9_68") (pintype "bidirectional"))
    )
    (net (code "165") (name "unconnected-(J1-ID-Pad4)") (class "Default")
      (node (ref "J1") (pin "4") (pinfunction "ID_4") (pintype "bidirectional"))
    )
    (net (code "166") (name "unconnected-(U$2-PadMS1)") (class "Default")
      (node (ref "U$2") (pin "MS1") (pinfunction "MS1_MS1") (pintype "input"))
    )
    (net (code "167") (name "unconnected-(U$2-PadMS2)") (class "Default")
      (node (ref "U$2") (pin "MS2") (pinfunction "MS2_MS2") (pintype "input"))
    )
    (net (code "168") (name "unconnected-(U$2-PadMS3)") (class "Default")
      (node (ref "U$2") (pin "MS3") (pinfunction "MS3_MS3") (pintype "input"))
    )
    (net (code "169") (name "unconnected-(U$3-PadMS1)") (class "Default")
      (node (ref "U$3") (pin "MS1") (pinfunction "MS1_MS1") (pintype "input"))
    )
    (net (code "170") (name "unconnected-(U$3-PadMS2)") (class "Default")
      (node (ref "U$3") (pin "MS2") (pinfunction "MS2_MS2") (pintype "input"))
    )
    (net (code "171") (name "unconnected-(U$3-PadMS3)") (class "Default")
      (node (ref "U$3") (pin "MS3") (pinfunction "MS3_MS3") (pintype "input"))
    )
    (net (code "172") (name "unconnected-(U$4-PadMS1)") (class "Default")
      (node (ref "U$4") (pin "MS1") (pinfunction "MS1_MS1") (pintype "input"))
    )
    (net (code "173") (name "unconnected-(U$4-PadMS2)") (class "Default")
      (node (ref "U$4") (pin "MS2") (pinfunction "MS2_MS2") (pintype "input"))
    )
    (net (code "174") (name "unconnected-(U$4-PadMS3)") (class "Default")
      (node (ref "U$4") (pin "MS3") (pinfunction "MS3_MS3") (pintype "input"))
    )
    (net (code "175") (name "unconnected-(U$5-PadMS1)") (class "Default")
      (node (ref "U$5") (pin "MS1") (pinfunction "MS1_MS1") (pintype "input"))
    )
    (net (code "176") (name "unconnected-(U$5-PadMS2)") (class "Default")
      (node (ref "U$5") (pin "MS2") (pinfunction "MS2_MS2") (pintype "input"))
    )
    (net (code "177") (name "unconnected-(U$5-PadMS3)") (class "Default")
      (node (ref "U$5") (pin "MS3") (pinfunction "MS3_MS3") (pintype "input"))
    )
    (net (code "178") (name "unconnected-(U$6-PadMS1)") (class "Default")
      (node (ref "U$6") (pin "MS1") (pinfunction "MS1_MS1") (pintype "input"))
    )
    (net (code "179") (name "unconnected-(U$6-PadMS2)") (class "Default")
      (node (ref "U$6") (pin "MS2") (pinfunction "MS2_MS2") (pintype "input"))
    )
    (net (code "180") (name "unconnected-(U$6-PadMS3)") (class "Default")
      (node (ref "U$6") (pin "MS3") (pinfunction "MS3_MS3") (pintype "input"))
    )
    (net (code "181") (name "unconnected-(U$7-PadMS1)") (class "Default")
      (node (ref "U$7") (pin "MS1") (pinfunction "MS1_MS1") (pintype "input"))
    )
    (net (code "182") (name "unconnected-(U$7-PadMS2)") (class "Default")
      (node (ref "U$7") (pin "MS2") (pinfunction "MS2_MS2") (pintype "input"))
    )
    (net (code "183") (name "unconnected-(U$7-PadMS3)") (class "Default")
      (node (ref "U$7") (pin "MS3") (pinfunction "MS3_MS3") (pintype "input"))
    )
    (net (code "184") (name "unconnected-(U$8-PadMS1)") (class "Default")
      (node (ref "U$8") (pin "MS1") (pinfunction "MS1_MS1") (pintype "input"))
    )
    (net (code "185") (name "unconnected-(U$8-PadMS2)") (class "Default")
      (node (ref "U$8") (pin "MS2") (pinfunction "MS2_MS2") (pintype "input"))
    )
    (net (code "186") (name "unconnected-(U$8-PadMS3)") (class "Default")
      (node (ref "U$8") (pin "MS3") (pinfunction "MS3_MS3") (pintype "input"))
    )
    (net (code "187") (name "unconnected-(U$9-PadMS1)") (class "Default")
      (node (ref "U$9") (pin "MS1") (pinfunction "MS1_MS1") (pintype "input"))
    )
    (net (code "188") (name "unconnected-(U$9-PadMS2)") (class "Default")
      (node (ref "U$9") (pin "MS2") (pinfunction "MS2_MS2") (pintype "input"))
    )
    (net (code "189") (name "unconnected-(U$9-PadMS3)") (class "Default")
      (node (ref "U$9") (pin "MS3") (pinfunction "MS3_MS3") (pintype "input"))
    )
    (net (code "190") (name "unconnected-(U1A-PA8-Pad67)") (class "Default")
      (node (ref "U1") (pin "67") (pinfunction "PA8_67") (pintype "bidirectional"))
    )
    (net (code "191") (name "unconnected-(U1A-PA12-Pad71)") (class "Default")
      (node (ref "U1") (pin "71") (pinfunction "PA12_71") (pintype "bidirectional"))
    )
    (net (code "192") (name "unconnected-(U1A-PA15-Pad77)") (class "Default")
      (node (ref "U1") (pin "77") (pinfunction "PA15_77") (pintype "bidirectional"))
    )
    (net (code "193") (name "unconnected-(U1A-PB1-Pad36)") (class "Default")
      (node (ref "U1") (pin "36") (pinfunction "PB1_36") (pintype "bidirectional"))
    )
    (net (code "194") (name "unconnected-(U1A-PB2-Pad37)") (class "Default")
      (node (ref "U1") (pin "37") (pinfunction "PB2_37") (pintype "bidirectional"))
    )
    (net (code "195") (name "unconnected-(U1A-PB3-Pad89)") (class "Default")
      (node (ref "U1") (pin "89") (pinfunction "PB3_89") (pintype "bidirectional"))
    )
    (net (code "196") (name "unconnected-(U1A-PB10-Pad47)") (class "Default")
      (node (ref "U1") (pin "47") (pinfunction "PB10_47") (pintype "bidirectional"))
    )
    (net (code "197") (name "unconnected-(U1A-PB13-Pad52)") (class "Default")
      (node (ref "U1") (pin "52") (pinfunction "PB13_52") (pintype "bidirectional"))
    )
    (net (code "198") (name "unconnected-(U1A-PB14-Pad53)") (class "Default")
      (node (ref "U1") (pin "53") (pinfunction "PB14_53") (pintype "bidirectional"))
    )
    (net (code "199") (name "unconnected-(U1A-PB15-Pad54)") (class "Default")
      (node (ref "U1") (pin "54") (pinfunction "PB15_54") (pintype "bidirectional"))
    )
    (net (code "200") (name "unconnected-(U1A-PC0-Pad15)") (class "Default")
      (node (ref "U1") (pin "15") (pinfunction "PC0_15") (pintype "bidirectional"))
    )
    (net (code "201") (name "unconnected-(U1A-PC1-Pad16)") (class "Default")
      (node (ref "U1") (pin "16") (pinfunction "PC1_16") (pintype "bidirectional"))
    )
    (net (code "202") (name "unconnected-(U1A-PC2-Pad17)") (class "Default")
      (node (ref "U1") (pin "17") (pinfunction "PC2_17") (pintype "bidirectional"))
    )
    (net (code "203") (name "unconnected-(U1A-PC3-Pad18)") (class "Default")
      (node (ref "U1") (pin "18") (pinfunction "PC3_18") (pintype "bidirectional"))
    )
    (net (code "204") (name "unconnected-(U1A-PC10-Pad78)") (class "Default")
      (node (ref "U1") (pin "78") (pinfunction "PC10_78") (pintype "bidirectional"))
    )
    (net (code "205") (name "unconnected-(U1A-PC13-Pad7)") (class "Default")
      (node (ref "U1") (pin "7") (pinfunction "PC13_7") (pintype "bidirectional"))
    )
    (net (code "206") (name "unconnected-(U1A-PC14-OSC32_IN-Pad8)") (class "Default")
      (node (ref "U1") (pin "8") (pinfunction "PC14-OSC32_IN_8") (pintype "bidirectional"))
    )
    (net (code "207") (name "unconnected-(U1A-PC15-OSC32_OUT-Pad9)") (class "Default")
      (node (ref "U1") (pin "9") (pinfunction "PC15-OSC32_OUT_9") (pintype "bidirectional"))
    )
    (net (code "208") (name "unconnected-(U1B-PE7-Pad38)") (class "Default")
      (node (ref "U1") (pin "38") (pinfunction "PE7_38") (pintype "bidirectional"))
    )
    (net (code "209") (name "unconnected-(U1B-PE8-Pad39)") (class "Default")
      (node (ref "U1") (pin "39") (pinfunction "PE8_39") (pintype "bidirectional"))
    )
    (net (code "210") (name "unconnected-(U1B-PE9-Pad40)") (class "Default")
      (node (ref "U1") (pin "40") (pinfunction "PE9_40") (pintype "bidirectional"))
    )
    (net (code "211") (name "unconnected-(U1B-PE10-Pad41)") (class "Default")
      (node (ref "U1") (pin "41") (pinfunction "PE10_41") (pintype "bidirectional"))
    )
    (net (code "212") (name "unconnected-(U1B-PE11-Pad42)") (class "Default")
      (node (ref "U1") (pin "42") (pinfunction "PE11_42") (pintype "bidirectional"))
    )
    (net (code "213") (name "unconnected-(U1B-PE12-Pad43)") (class "Default")
      (node (ref "U1") (pin "43") (pinfunction "PE12_43") (pintype "bidirectional"))
    )
    (net (code "214") (name "unconnected-(U2-CTS#-Pad9)") (class "Default")
      (node (ref "U2") (pin "9") (pinfunction "CTS#_9") (pintype "bidirectional"))
    )
    (net (code "215") (name "unconnected-(U2-DCD#-Pad12)") (class "Default")
      (node (ref "U2") (pin "12") (pinfunction "DCD#_12") (pintype "bidirectional"))
    )
    (net (code "216") (name "unconnected-(U2-DSR#-Pad10)") (class "Default")
      (node (ref "U2") (pin "10") (pinfunction "DSR#_10") (pintype "bidirectional"))
    )
    (net (code "217") (name "unconnected-(U2-R232-Pad15)") (class "Default")
      (node (ref "U2") (pin "15") (pinfunction "R232_15") (pintype "bidirectional"))
    )
    (net (code "218") (name "unconnected-(U2-RI#-Pad11)") (class "Default")
      (node (ref "U2") (pin "11") (pinfunction "RI#_11") (pintype "bidirectional"))
    )
    (net (code "219") (name "unconnected-(U2-RTS#-Pad14)") (class "Default")
      (node (ref "U2") (pin "14") (pinfunction "RTS#_14") (pintype "bidirectional"))
    )
  )
)
